# DIO-BNC.net
KiCad netlist of a schematic drawn in Altium Designer
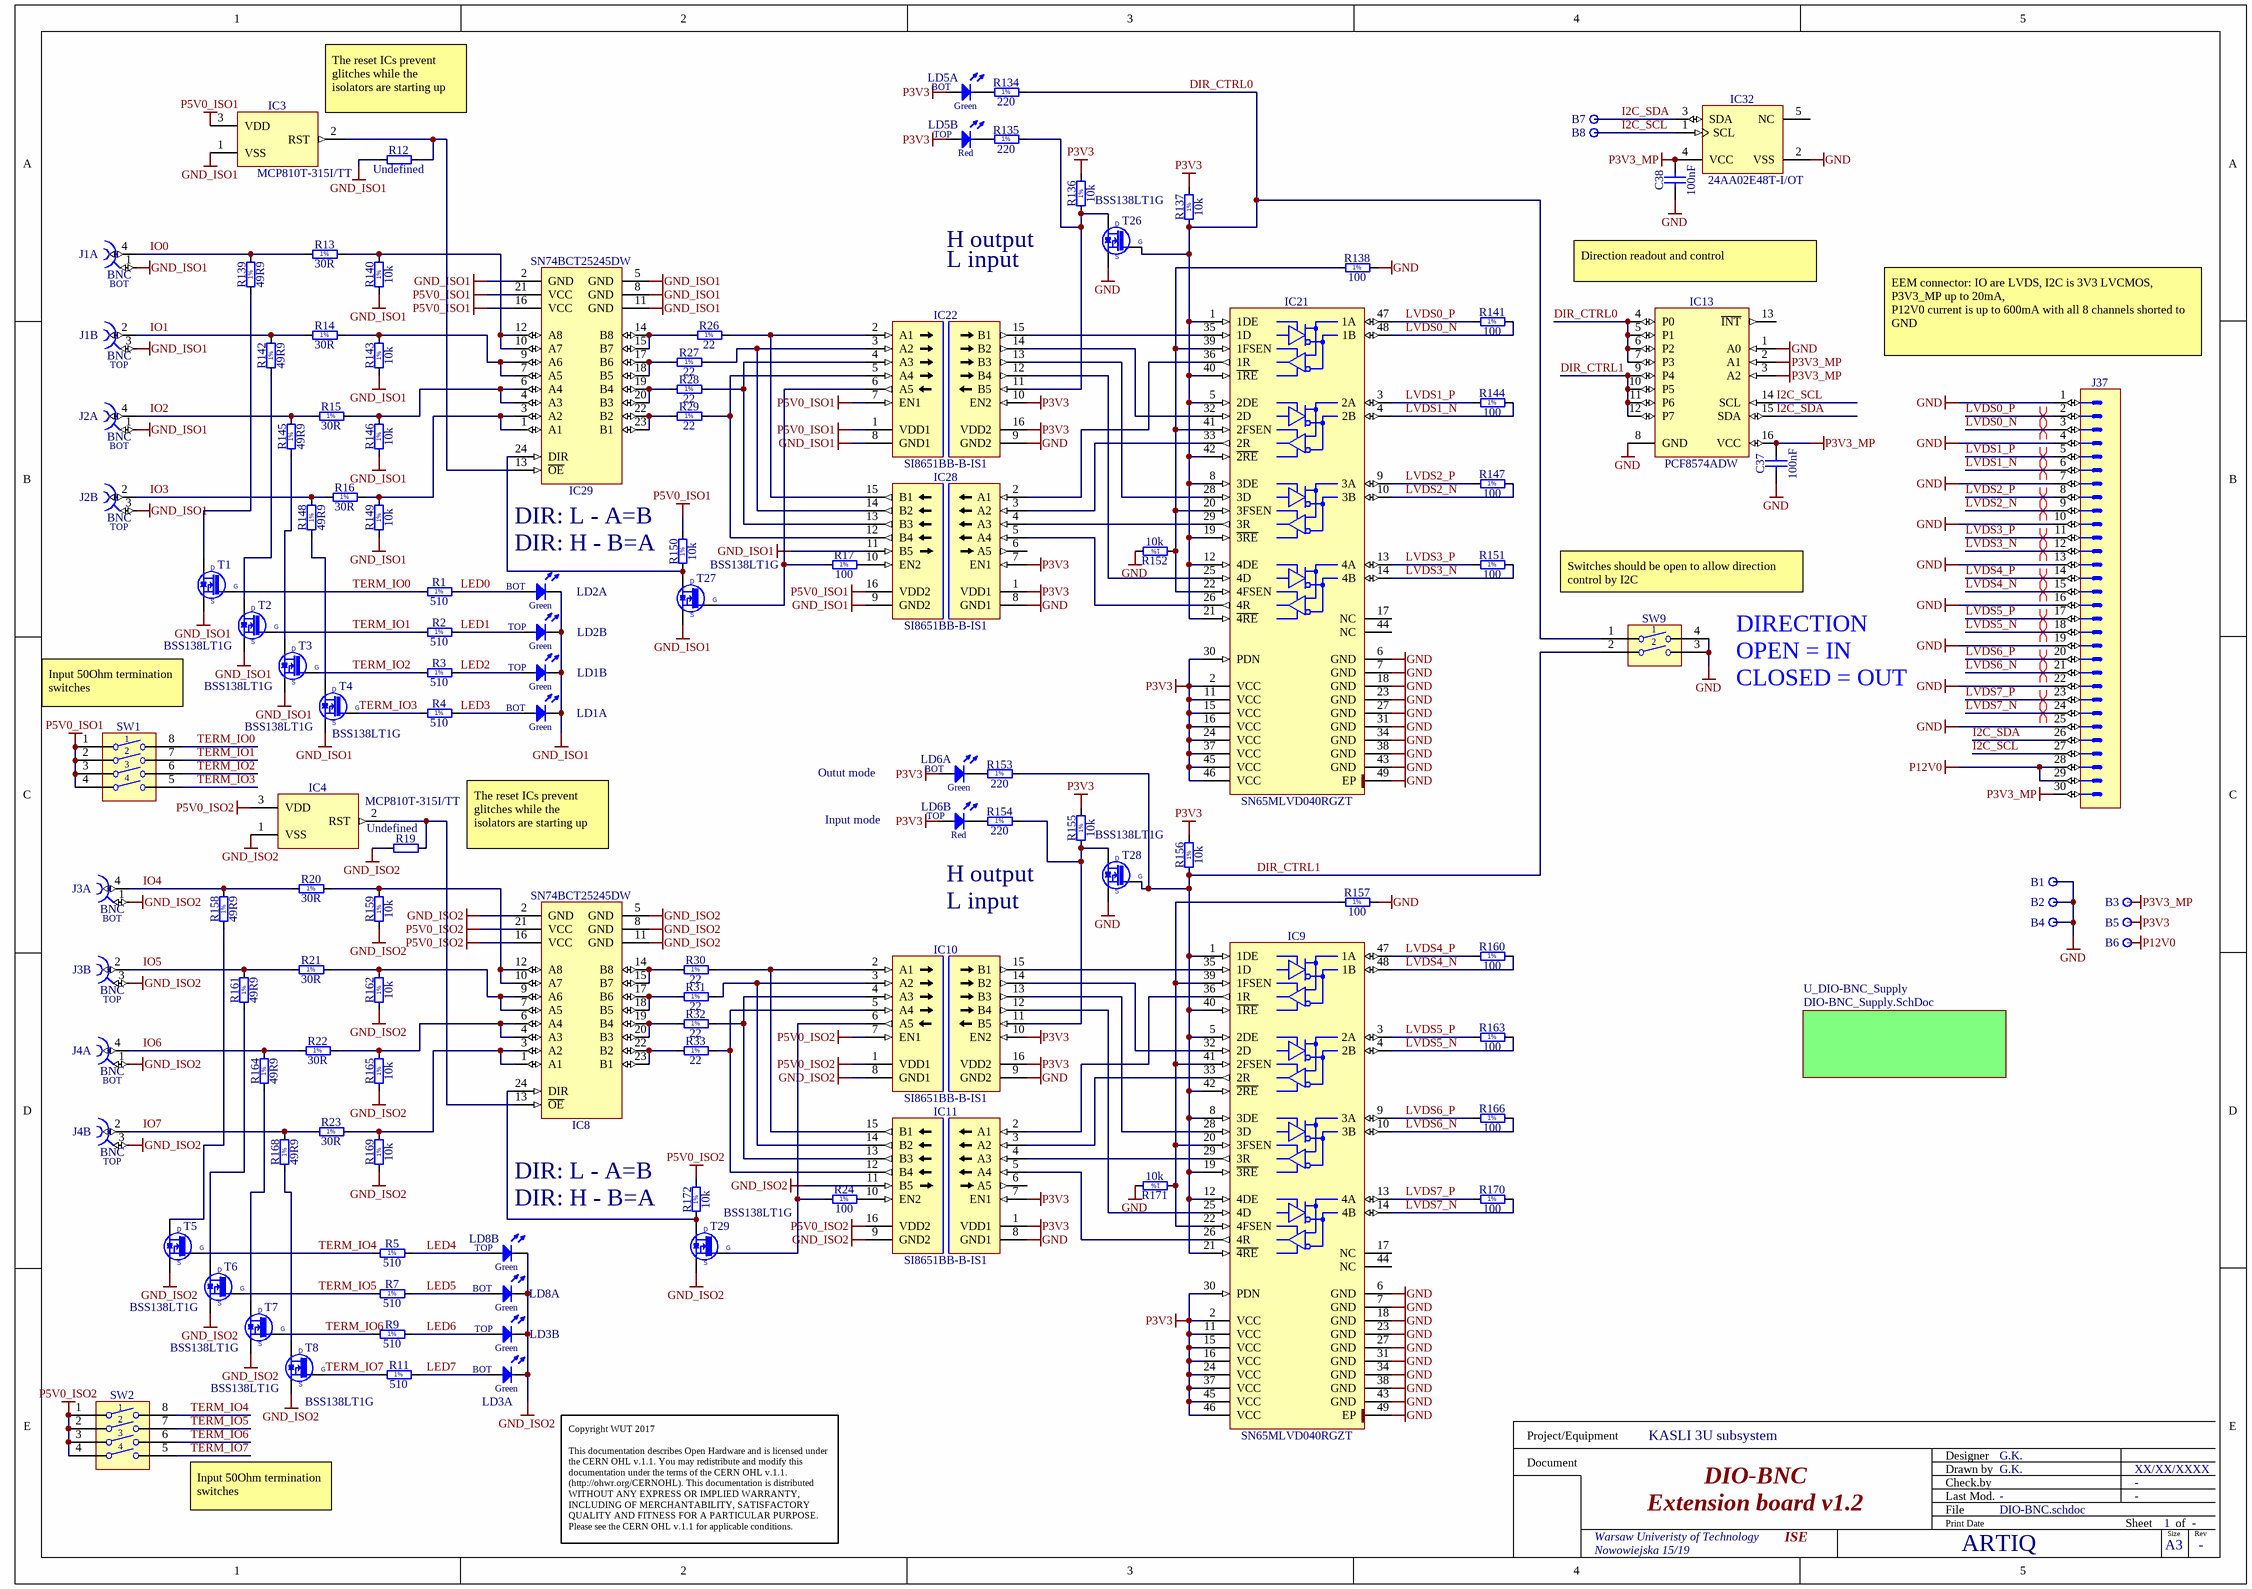
[diagram p0: DIO-BNC.schdoc]

(export (version "E")
  (design (tool "Eeschema 10.0.6"))
  (components
    (comp (ref "B1")
      (value "Plated Hole")
      (footprint "c130h60")
      (description "Single Terminal Socket")
      (fields (field (name "PART NUMBER") "PLATED_HOLE0.6_PAD1.3") (field (name "AUTHOR") "CERN DEM MR"))
      (libsource (lib "Eletro-mechanical") (part "Single Terminal Socket"))
    )
    (comp (ref "B2")
      (value "Plated Hole")
      (footprint "c130h60")
      (description "Single Terminal Socket")
      (fields (field (name "PART NUMBER") "PLATED_HOLE0.6_PAD1.3") (field (name "AUTHOR") "CERN DEM MR"))
      (libsource (lib "Eletro-mechanical") (part "Single Terminal Socket"))
    )
    (comp (ref "B3")
      (value "Plated Hole")
      (footprint "c130h60")
      (description "Single Terminal Socket")
      (fields (field (name "PART NUMBER") "PLATED_HOLE0.6_PAD1.3") (field (name "AUTHOR") "CERN DEM MR"))
      (libsource (lib "Eletro-mechanical") (part "Single Terminal Socket"))
    )
    (comp (ref "B4")
      (value "Plated Hole")
      (footprint "c130h60")
      (description "Single Terminal Socket")
      (fields (field (name "PART NUMBER") "PLATED_HOLE0.6_PAD1.3") (field (name "AUTHOR") "CERN DEM MR"))
      (libsource (lib "Eletro-mechanical") (part "Single Terminal Socket"))
    )
    (comp (ref "B5")
      (value "Plated Hole")
      (footprint "c130h60")
      (description "Single Terminal Socket")
      (fields (field (name "PART NUMBER") "PLATED_HOLE0.6_PAD1.3") (field (name "AUTHOR") "CERN DEM MR"))
      (libsource (lib "Eletro-mechanical") (part "Single Terminal Socket"))
    )
    (comp (ref "B6")
      (value "Plated Hole")
      (footprint "c130h60")
      (description "Single Terminal Socket")
      (fields (field (name "PART NUMBER") "PLATED_HOLE0.6_PAD1.3") (field (name "AUTHOR") "CERN DEM MR"))
      (libsource (lib "Eletro-mechanical") (part "Single Terminal Socket"))
    )
    (comp (ref "B7")
      (value "Plated Hole")
      (footprint "c130h60")
      (description "Single Terminal Socket")
      (fields (field (name "PART NUMBER") "PLATED_HOLE0.6_PAD1.3") (field (name "AUTHOR") "CERN DEM MR"))
      (libsource (lib "Eletro-mechanical") (part "Single Terminal Socket"))
    )
    (comp (ref "B8")
      (value "Plated Hole")
      (footprint "c130h60")
      (description "Single Terminal Socket")
      (fields (field (name "PART NUMBER") "PLATED_HOLE0.6_PAD1.3") (field (name "AUTHOR") "CERN DEM MR"))
      (libsource (lib "Eletro-mechanical") (part "Single Terminal Socket"))
    )
    (comp (ref "C37")
      (value "100nF")
      (footprint "CAPC1005X55N")
      (description "Non-polarised capacitor")
      (fields
        (field (name "PART NUMBER") "CC0402_100NF_16V_10%_X5R")
        (field (name "VOLTAGE") "16V")
        (field (name "AUTHOR") "CERN DEM JLC")
      )
      (libsource (lib "Capacitors") (part "Capacitor - non polarized"))
    )
    (comp (ref "C38")
      (value "100nF")
      (footprint "CAPC1005X55N")
      (description "Non-polarised capacitor")
      (fields
        (field (name "PART NUMBER") "CC0402_100NF_16V_10%_X5R")
        (field (name "VOLTAGE") "16V")
        (field (name "AUTHOR") "CERN DEM JLC")
      )
      (libsource (lib "Capacitors") (part "Capacitor - non polarized"))
    )
    (comp (ref "IC3")
      (value "MCP810T-315I/TT")
      (footprint "SOT95P237X112-3N")
      (description "3.075V Microcontroller Supervisory Circuit With Push-Pull Output")
      (fields (field (name "MANUFACTURER") "MICROCHIP TECHNOLOGY") (field (name "AUTHOR") "GK"))
      (libsource (lib "LIBRARY_SCH") (part "VMON_MCP810"))
    )
    (comp (ref "IC4")
      (value "MCP810T-315I/TT")
      (footprint "SOT95P237X112-3N")
      (description "3.075V Microcontroller Supervisory Circuit With Push-Pull Output")
      (fields (field (name "MANUFACTURER") "MICROCHIP TECHNOLOGY") (field (name "AUTHOR") "GK"))
      (libsource (lib "LIBRARY_SCH") (part "VMON_MCP810"))
    )
    (comp (ref "IC8")
      (value "SN74BCT25245DW")
      (footprint "SOIC127P1030X265-24N")
      (description "25 Ohms Octal Bus Transceiver With 3-State Outputs")
      (fields (field (name "MANUFACTURER") "TEXAS INSTRUMENTS") (field (name "AUTHOR") "CERN DEM JLC"))
      (libsource (lib "ICs And Semiconductors") (part "7425245"))
    )
    (comp (ref "IC9")
      (value "SN65MLVD040RGZT")
      (footprint "QFN50P700X700X100-49N-S420")
      (description "4-Channel Half-Duplex M-LVDS Line Transceiver")
      (fields (field (name "MANUFACTURER") "TEXAS INSTRUMENTS") (field (name "AUTHOR") "CERN DEM JLC"))
      (libsource (lib "ICs And Semiconductors") (part "SN65MLVD040"))
    )
    (comp (ref "IC10")
      (value "SI8651BB-B-IS1")
      (footprint "SOIC127P600X175-16N")
      (description "Low Power Five-Channel Digital Isolator")
      (fields (field (name "MANUFACTURER") "SILICON LABS") (field (name "AUTHOR") "CERN DEM JLC"))
      (libsource (lib "") (part "Si8651_1"))
    )
    (comp (ref "IC11")
      (value "SI8651BB-B-IS1")
      (footprint "SOIC127P600X175-16N")
      (description "Low Power Five-Channel Digital Isolator")
      (fields (field (name "MANUFACTURER") "SILICON LABS") (field (name "AUTHOR") "CERN DEM JLC"))
      (libsource (lib "ICs And Semiconductors") (part "Si8651"))
    )
    (comp (ref "IC13")
      (value "PCF8574ADW")
      (footprint "SOIC127P1030X265-16N")
      (description "Remote 8-bit I/O Expander For I2C Bus")
      (fields (field (name "MANUFACTURER") "TEXAS INSTRUMENTS") (field (name "AUTHOR") "CERN DEM JLC"))
      (libsource (lib "ICs And Semiconductors") (part "PCF8574ADW"))
    )
    (comp (ref "IC21")
      (value "SN65MLVD040RGZT")
      (footprint "QFN50P700X700X100-49N-S420")
      (description "4-Channel Half-Duplex M-LVDS Line Transceiver")
      (fields (field (name "MANUFACTURER") "TEXAS INSTRUMENTS") (field (name "AUTHOR") "CERN DEM JLC"))
      (libsource (lib "ICs And Semiconductors") (part "SN65MLVD040"))
    )
    (comp (ref "IC22")
      (value "SI8651BB-B-IS1")
      (footprint "SOIC127P600X175-16N")
      (description "Low Power Five-Channel Digital Isolator")
      (fields (field (name "MANUFACTURER") "SILICON LABS") (field (name "AUTHOR") "CERN DEM JLC"))
      (libsource (lib "") (part "Si8651_1"))
    )
    (comp (ref "IC28")
      (value "SI8651BB-B-IS1")
      (footprint "SOIC127P600X175-16N")
      (description "Low Power Five-Channel Digital Isolator")
      (fields (field (name "MANUFACTURER") "SILICON LABS") (field (name "AUTHOR") "CERN DEM JLC"))
      (libsource (lib "ICs And Semiconductors") (part "Si8651"))
    )
    (comp (ref "IC29")
      (value "SN74BCT25245DW")
      (footprint "SOIC127P1030X265-24N")
      (description "25 Ohms Octal Bus Transceiver With 3-State Outputs")
      (fields (field (name "MANUFACTURER") "TEXAS INSTRUMENTS") (field (name "AUTHOR") "CERN DEM JLC"))
      (libsource (lib "ICs And Semiconductors") (part "7425245"))
    )
    (comp (ref "IC32")
      (value "24AA02E48T-I/OT")
      (footprint "SOT95P280X145-5N")
      (description "1.7V-5.5V, 2K I2C Serial EEPROM With EUI-48 Node Identity")
      (fields (field (name "MANUFACTURER") "MICROCHIP TECHNOLOGY") (field (name "AUTHOR") "CERN DEM MR"))
      (libsource (lib "ICs And Semiconductors") (part "24AA02E48T-I/OT"))
    )
    (comp (ref "J1")
      (value "BNC")
      (footprint "RENHOTEC_RHT-610-0049")
      (description "Dual Right Angle 50 Ohm BNC Jack, White Valox Case")
      (fields
        (field (name "PART NUMBER") "RENHOTEC_RHT-610-0049")
        (field (name "MANUFACTURER") "RENHOTEC")
        (field (name "AUTHOR") "GK")
      )
      (libsource (lib "LIBRARY_SCH") (part "CON_BNC_DUAL"))
    )
    (comp (ref "J2")
      (value "BNC")
      (footprint "RENHOTEC_RHT-610-0049")
      (description "Dual Right Angle 50 Ohm BNC Jack, White Valox Case")
      (fields
        (field (name "PART NUMBER") "RENHOTEC_RHT-610-0049")
        (field (name "MANUFACTURER") "RENHOTEC")
        (field (name "AUTHOR") "GK")
      )
      (libsource (lib "LIBRARY_SCH") (part "CON_BNC_DUAL"))
    )
    (comp (ref "J3")
      (value "BNC")
      (footprint "RENHOTEC_RHT-610-0049")
      (description "Dual Right Angle 50 Ohm BNC Jack, White Valox Case")
      (fields
        (field (name "PART NUMBER") "RENHOTEC_RHT-610-0049")
        (field (name "MANUFACTURER") "RENHOTEC")
        (field (name "AUTHOR") "GK")
      )
      (libsource (lib "LIBRARY_SCH") (part "CON_BNC_DUAL"))
    )
    (comp (ref "J4")
      (value "BNC")
      (footprint "RENHOTEC_RHT-610-0049")
      (description "Dual Right Angle 50 Ohm BNC Jack, White Valox Case")
      (fields
        (field (name "PART NUMBER") "RENHOTEC_RHT-610-0049")
        (field (name "MANUFACTURER") "RENHOTEC")
        (field (name "AUTHOR") "GK")
      )
      (libsource (lib "LIBRARY_SCH") (part "CON_BNC_DUAL"))
    )
    (comp (ref "J37")
      (value "~")
      (footprint "3M_N2530-6002RB")
      (description "Connector 30 Male")
      (fields
        (field (name "PART NUMBER") "3M_N2530-6002RB")
        (field (name "MANUFACTURER") "3M")
        (field (name "AUTHOR") "CERN DEM JLC")
      )
      (libsource (lib "Connectors") (part "Connector 30 Male"))
    )
    (comp (ref "LD1")
      (value "Green/Green")
      (footprint "LED_DIALIGHT_571-0122F")
      (description "LED x2 Green 1C2A-BOT_3C4A-TOP")
      (fields
        (field (name "PART NUMBER") "LED_DIALIGHT_571-0122F")
        (field (name "MANUFACTURER") "DIALIGHT")
        (field (name "AUTHOR") "CERN DEM JLC")
      )
      (libsource (lib "ICs And Semiconductors") (part "LED x2 Green 1C2A-BOT_3C4A-TOP"))
    )
    (comp (ref "LD2")
      (value "Green/Green")
      (footprint "LED_DIALIGHT_571-0122F")
      (description "LED x2 Green 1C2A-BOT_3C4A-TOP")
      (fields
        (field (name "PART NUMBER") "LED_DIALIGHT_571-0122F")
        (field (name "MANUFACTURER") "DIALIGHT")
        (field (name "AUTHOR") "CERN DEM JLC")
      )
      (libsource (lib "ICs And Semiconductors") (part "LED x2 Green 1C2A-BOT_3C4A-TOP"))
    )
    (comp (ref "LD3")
      (value "Green/Green")
      (footprint "LED_DIALIGHT_571-0122F")
      (description "LED x2 Green 1C2A-BOT_3C4A-TOP")
      (fields
        (field (name "PART NUMBER") "LED_DIALIGHT_571-0122F")
        (field (name "MANUFACTURER") "DIALIGHT")
        (field (name "AUTHOR") "CERN DEM JLC")
      )
      (libsource (lib "ICs And Semiconductors") (part "LED x2 Green 1C2A-BOT_3C4A-TOP"))
    )
    (comp (ref "LD5")
      (value "Red/Green")
      (footprint "LED_DIALIGHT_571-0112F")
      (description "2x LED  Botom Green, Top Red")
      (fields
        (field (name "PART NUMBER") "LED_DIALIGHT_571-0112F")
        (field (name "MANUFACTURER") "DIALIGHT")
        (field (name "AUTHOR") "CERN DEM JLC")
      )
      (libsource (lib "ICs And Semiconductors") (part "LED x2 G-1C2A-BOT_R-3C4A-TOP"))
    )
    (comp (ref "LD6")
      (value "Red/Green")
      (footprint "LED_DIALIGHT_571-0112F")
      (description "2x LED  Botom Green, Top Red")
      (fields
        (field (name "PART NUMBER") "LED_DIALIGHT_571-0112F")
        (field (name "MANUFACTURER") "DIALIGHT")
        (field (name "AUTHOR") "CERN DEM JLC")
      )
      (libsource (lib "ICs And Semiconductors") (part "LED x2 G-1C2A-BOT_R-3C4A-TOP"))
    )
    (comp (ref "LD8")
      (value "Green/Green")
      (footprint "LED_DIALIGHT_571-0122F")
      (description "LED x2 Green 1C2A-BOT_3C4A-TOP")
      (fields
        (field (name "PART NUMBER") "LED_DIALIGHT_571-0122F")
        (field (name "MANUFACTURER") "DIALIGHT")
        (field (name "AUTHOR") "CERN DEM JLC")
      )
      (libsource (lib "ICs And Semiconductors") (part "LED x2 Green 1C2A-BOT_3C4A-TOP"))
    )
    (comp (ref "R1")
      (value "510")
      (footprint "RESC1005X40N")
      (description "Resistor - 1%")
      (fields
        (field (name "PART NUMBER") "R0402_510R_1%_0.0625W_100PPM")
        (field (name "POWER") "0.0625W")
        (field (name "AUTHOR") "CERN DEM JLC")
      )
      (libsource (lib "Resistors") (part "Resistor - 1%"))
    )
    (comp (ref "R2")
      (value "510")
      (footprint "RESC1005X40N")
      (description "Resistor - 1%")
      (fields
        (field (name "PART NUMBER") "R0402_510R_1%_0.0625W_100PPM")
        (field (name "POWER") "0.0625W")
        (field (name "AUTHOR") "CERN DEM JLC")
      )
      (libsource (lib "Resistors") (part "Resistor - 1%"))
    )
    (comp (ref "R3")
      (value "510")
      (footprint "RESC1005X40N")
      (description "Resistor - 1%")
      (fields
        (field (name "PART NUMBER") "R0402_510R_1%_0.0625W_100PPM")
        (field (name "POWER") "0.0625W")
        (field (name "AUTHOR") "CERN DEM JLC")
      )
      (libsource (lib "Resistors") (part "Resistor - 1%"))
    )
    (comp (ref "R4")
      (value "510")
      (footprint "RESC1005X40N")
      (description "Resistor - 1%")
      (fields
        (field (name "PART NUMBER") "R0402_510R_1%_0.0625W_100PPM")
        (field (name "POWER") "0.0625W")
        (field (name "AUTHOR") "CERN DEM JLC")
      )
      (libsource (lib "Resistors") (part "Resistor - 1%"))
    )
    (comp (ref "R5")
      (value "510")
      (footprint "RESC1005X40N")
      (description "Resistor - 1%")
      (fields
        (field (name "PART NUMBER") "R0402_510R_1%_0.0625W_100PPM")
        (field (name "POWER") "0.0625W")
        (field (name "AUTHOR") "CERN DEM JLC")
      )
      (libsource (lib "Resistors") (part "Resistor - 1%"))
    )
    (comp (ref "R7")
      (value "510")
      (footprint "RESC1005X40N")
      (description "Resistor - 1%")
      (fields
        (field (name "PART NUMBER") "R0402_510R_1%_0.0625W_100PPM")
        (field (name "POWER") "0.0625W")
        (field (name "AUTHOR") "CERN DEM JLC")
      )
      (libsource (lib "Resistors") (part "Resistor - 1%"))
    )
    (comp (ref "R9")
      (value "510")
      (footprint "RESC1005X40N")
      (description "Resistor - 1%")
      (fields
        (field (name "PART NUMBER") "R0402_510R_1%_0.0625W_100PPM")
        (field (name "POWER") "0.0625W")
        (field (name "AUTHOR") "CERN DEM JLC")
      )
      (libsource (lib "Resistors") (part "Resistor - 1%"))
    )
    (comp (ref "R11")
      (value "510")
      (footprint "RESC1005X40N")
      (description "Resistor - 1%")
      (fields
        (field (name "PART NUMBER") "R0402_510R_1%_0.0625W_100PPM")
        (field (name "POWER") "0.0625W")
        (field (name "AUTHOR") "CERN DEM JLC")
      )
      (libsource (lib "Resistors") (part "Resistor - 1%"))
    )
    (comp (ref "R12")
      (value "Undefined")
      (footprint "RESC1005X40N")
      (description "Resistor")
      (fields (field (name "PART NUMBER") "R0402_NO-VALUE") (field (name "AUTHOR") "CERN DEM JLC"))
      (libsource (lib "Resistors") (part "Resistor"))
    )
    (comp (ref "R13")
      (value "30R")
      (footprint "RESC3225X70N")
      (description "Resistor - 5%")
      (fields
        (field (name "PART NUMBER") "R1210_30R_5%_0.5W_200ppm")
        (field (name "POWER") "0.5W")
        (field (name "AUTHOR") "CERN DEM JMW")
      )
      (libsource (lib "LIBRARY_SCH") (part "R1210_30R_5%_0.5W_200PPM"))
    )
    (comp (ref "R14")
      (value "30R")
      (footprint "RESC3225X70N")
      (description "Resistor - 5%")
      (fields
        (field (name "PART NUMBER") "R1210_30R_5%_0.5W_200ppm")
        (field (name "POWER") "0.5W")
        (field (name "AUTHOR") "CERN DEM JMW")
      )
      (libsource (lib "LIBRARY_SCH") (part "R1210_30R_5%_0.5W_200PPM"))
    )
    (comp (ref "R15")
      (value "30R")
      (footprint "RESC3225X70N")
      (description "Resistor - 5%")
      (fields
        (field (name "PART NUMBER") "R1210_30R_5%_0.5W_200ppm")
        (field (name "POWER") "0.5W")
        (field (name "AUTHOR") "CERN DEM JMW")
      )
      (libsource (lib "LIBRARY_SCH") (part "R1210_30R_5%_0.5W_200PPM"))
    )
    (comp (ref "R16")
      (value "30R")
      (footprint "RESC3225X70N")
      (description "Resistor - 5%")
      (fields
        (field (name "PART NUMBER") "R1210_30R_5%_0.5W_200ppm")
        (field (name "POWER") "0.5W")
        (field (name "AUTHOR") "CERN DEM JMW")
      )
      (libsource (lib "LIBRARY_SCH") (part "R1210_30R_5%_0.5W_200PPM"))
    )
    (comp (ref "R17")
      (value "100")
      (footprint "RESC1005X40N")
      (description "Resistor - 1%")
      (fields
        (field (name "PART NUMBER") "R0402_100R_1%_0.1W_100PPM")
        (field (name "POWER") "0.1W")
        (field (name "AUTHOR") "CERN DEM JLC")
      )
      (libsource (lib "Resistors") (part "Resistor - 1%"))
    )
    (comp (ref "R19")
      (value "Undefined")
      (footprint "RESC1005X40N")
      (description "Resistor")
      (fields (field (name "PART NUMBER") "R0402_NO-VALUE") (field (name "AUTHOR") "CERN DEM JLC"))
      (libsource (lib "Resistors") (part "Resistor"))
    )
    (comp (ref "R20")
      (value "30R")
      (footprint "RESC3225X70N")
      (description "Resistor - 5%")
      (fields
        (field (name "PART NUMBER") "R1210_30R_5%_0.5W_200ppm")
        (field (name "POWER") "0.5W")
        (field (name "AUTHOR") "CERN DEM JMW")
      )
      (libsource (lib "LIBRARY_SCH") (part "R1210_30R_5%_0.5W_200PPM"))
    )
    (comp (ref "R21")
      (value "30R")
      (footprint "RESC3225X70N")
      (description "Resistor - 5%")
      (fields
        (field (name "PART NUMBER") "R1210_30R_5%_0.5W_200ppm")
        (field (name "POWER") "0.5W")
        (field (name "AUTHOR") "CERN DEM JMW")
      )
      (libsource (lib "LIBRARY_SCH") (part "R1210_30R_5%_0.5W_200PPM"))
    )
    (comp (ref "R22")
      (value "30R")
      (footprint "RESC3225X70N")
      (description "Resistor - 5%")
      (fields
        (field (name "PART NUMBER") "R1210_30R_5%_0.5W_200ppm")
        (field (name "POWER") "0.5W")
        (field (name "AUTHOR") "CERN DEM JMW")
      )
      (libsource (lib "LIBRARY_SCH") (part "R1210_30R_5%_0.5W_200PPM"))
    )
    (comp (ref "R23")
      (value "30R")
      (footprint "RESC3225X70N")
      (description "Resistor - 5%")
      (fields
        (field (name "PART NUMBER") "R1210_30R_5%_0.5W_200ppm")
        (field (name "POWER") "0.5W")
        (field (name "AUTHOR") "CERN DEM JMW")
      )
      (libsource (lib "LIBRARY_SCH") (part "R1210_30R_5%_0.5W_200PPM"))
    )
    (comp (ref "R24")
      (value "100")
      (footprint "RESC1005X40N")
      (description "Resistor - 1%")
      (fields
        (field (name "PART NUMBER") "R0402_100R_1%_0.1W_100PPM")
        (field (name "POWER") "0.1W")
        (field (name "AUTHOR") "CERN DEM JLC")
      )
      (libsource (lib "Resistors") (part "Resistor - 1%"))
    )
    (comp (ref "R26")
      (value "22")
      (footprint "RESC1005X40N")
      (description "Resistor - 1%")
      (fields
        (field (name "PART NUMBER") "R0402_22R_1%_0.0625W_100PPM")
        (field (name "POWER") "0.0625W")
        (field (name "AUTHOR") "CERN DEM JLC")
      )
      (libsource (lib "Resistors") (part "Resistor - 1%"))
    )
    (comp (ref "R27")
      (value "22")
      (footprint "RESC1005X40N")
      (description "Resistor - 1%")
      (fields
        (field (name "PART NUMBER") "R0402_22R_1%_0.0625W_100PPM")
        (field (name "POWER") "0.0625W")
        (field (name "AUTHOR") "CERN DEM JLC")
      )
      (libsource (lib "Resistors") (part "Resistor - 1%"))
    )
    (comp (ref "R28")
      (value "22")
      (footprint "RESC1005X40N")
      (description "Resistor - 1%")
      (fields
        (field (name "PART NUMBER") "R0402_22R_1%_0.0625W_100PPM")
        (field (name "POWER") "0.0625W")
        (field (name "AUTHOR") "CERN DEM JLC")
      )
      (libsource (lib "Resistors") (part "Resistor - 1%"))
    )
    (comp (ref "R29")
      (value "22")
      (footprint "RESC1005X40N")
      (description "Resistor - 1%")
      (fields
        (field (name "PART NUMBER") "R0402_22R_1%_0.0625W_100PPM")
        (field (name "POWER") "0.0625W")
        (field (name "AUTHOR") "CERN DEM JLC")
      )
      (libsource (lib "Resistors") (part "Resistor - 1%"))
    )
    (comp (ref "R30")
      (value "22")
      (footprint "RESC1005X40N")
      (description "Resistor - 1%")
      (fields
        (field (name "PART NUMBER") "R0402_22R_1%_0.0625W_100PPM")
        (field (name "POWER") "0.0625W")
        (field (name "AUTHOR") "CERN DEM JLC")
      )
      (libsource (lib "Resistors") (part "Resistor - 1%"))
    )
    (comp (ref "R31")
      (value "22")
      (footprint "RESC1005X40N")
      (description "Resistor - 1%")
      (fields
        (field (name "PART NUMBER") "R0402_22R_1%_0.0625W_100PPM")
        (field (name "POWER") "0.0625W")
        (field (name "AUTHOR") "CERN DEM JLC")
      )
      (libsource (lib "Resistors") (part "Resistor - 1%"))
    )
    (comp (ref "R32")
      (value "22")
      (footprint "RESC1005X40N")
      (description "Resistor - 1%")
      (fields
        (field (name "PART NUMBER") "R0402_22R_1%_0.0625W_100PPM")
        (field (name "POWER") "0.0625W")
        (field (name "AUTHOR") "CERN DEM JLC")
      )
      (libsource (lib "Resistors") (part "Resistor - 1%"))
    )
    (comp (ref "R33")
      (value "22")
      (footprint "RESC1005X40N")
      (description "Resistor - 1%")
      (fields
        (field (name "PART NUMBER") "R0402_22R_1%_0.0625W_100PPM")
        (field (name "POWER") "0.0625W")
        (field (name "AUTHOR") "CERN DEM JLC")
      )
      (libsource (lib "Resistors") (part "Resistor - 1%"))
    )
    (comp (ref "R134")
      (value "220")
      (footprint "RESC1608X55N")
      (description "Resistor - 1%")
      (fields
        (field (name "PART NUMBER") "R0603_220R_1%_0.1W_100PPM")
        (field (name "POWER") "0.1W")
        (field (name "AUTHOR") "CERN DEM JLC")
      )
      (libsource (lib "Resistors") (part "Resistor - 1%"))
    )
    (comp (ref "R135")
      (value "220")
      (footprint "RESC1608X55N")
      (description "Resistor - 1%")
      (fields
        (field (name "PART NUMBER") "R0603_220R_1%_0.1W_100PPM")
        (field (name "POWER") "0.1W")
        (field (name "AUTHOR") "CERN DEM JLC")
      )
      (libsource (lib "Resistors") (part "Resistor - 1%"))
    )
    (comp (ref "R136")
      (value "10k")
      (footprint "RESC1005X40N")
      (description "Resistor - 1%")
      (fields
        (field (name "PART NUMBER") "R0402_10K_1%_0.0625W_100PPM")
        (field (name "POWER") "0.0625W")
        (field (name "AUTHOR") "CERN DEM JLC")
      )
      (libsource (lib "Resistors") (part "Resistor - 1%"))
    )
    (comp (ref "R137")
      (value "10k")
      (footprint "RESC1005X40N")
      (description "Resistor - 1%")
      (fields
        (field (name "PART NUMBER") "R0402_10K_1%_0.0625W_100PPM")
        (field (name "POWER") "0.0625W")
        (field (name "AUTHOR") "CERN DEM JLC")
      )
      (libsource (lib "Resistors") (part "Resistor - 1%"))
    )
    (comp (ref "R138")
      (value "100")
      (footprint "RESC1005X40N")
      (description "Resistor - 1%")
      (fields
        (field (name "PART NUMBER") "R0402_100R_1%_0.1W_100PPM")
        (field (name "POWER") "0.1W")
        (field (name "AUTHOR") "CERN DEM JLC")
      )
      (libsource (lib "Resistors") (part "Resistor - 1%"))
    )
    (comp (ref "R139")
      (value "49R9")
      (footprint "RESC3225X70N")
      (description "Resistor - 1%")
      (fields
        (field (name "PART NUMBER") "R1210_49R9_1%_0.5W_100PPM_VISHAY_CRCW")
        (field (name "POWER") "0.5W")
        (field (name "AUTHOR") "CERN DEM JMW")
      )
      (libsource (lib "Resistors") (part "Resistor - 1%"))
    )
    (comp (ref "R140")
      (value "10k")
      (footprint "RESC1005X40N")
      (description "Resistor - 1%")
      (fields
        (field (name "PART NUMBER") "R0402_10K_1%_0.0625W_100PPM")
        (field (name "POWER") "0.0625W")
        (field (name "AUTHOR") "CERN DEM JLC")
      )
      (libsource (lib "Resistors") (part "Resistor - 1%"))
    )
    (comp (ref "R141")
      (value "100")
      (footprint "RESC1005X40N")
      (description "Resistor - 1%")
      (fields
        (field (name "PART NUMBER") "R0402_100R_1%_0.1W_100PPM")
        (field (name "POWER") "0.1W")
        (field (name "AUTHOR") "CERN DEM JLC")
      )
      (libsource (lib "Resistors") (part "Resistor - 1%"))
    )
    (comp (ref "R142")
      (value "49R9")
      (footprint "RESC3225X70N")
      (description "Resistor - 1%")
      (fields
        (field (name "PART NUMBER") "R1210_49R9_1%_0.5W_100PPM_VISHAY_CRCW")
        (field (name "POWER") "0.5W")
        (field (name "AUTHOR") "CERN DEM JMW")
      )
      (libsource (lib "Resistors") (part "Resistor - 1%"))
    )
    (comp (ref "R143")
      (value "10k")
      (footprint "RESC1005X40N")
      (description "Resistor - 1%")
      (fields
        (field (name "PART NUMBER") "R0402_10K_1%_0.0625W_100PPM")
        (field (name "POWER") "0.0625W")
        (field (name "AUTHOR") "CERN DEM JLC")
      )
      (libsource (lib "Resistors") (part "Resistor - 1%"))
    )
    (comp (ref "R144")
      (value "100")
      (footprint "RESC1005X40N")
      (description "Resistor - 1%")
      (fields
        (field (name "PART NUMBER") "R0402_100R_1%_0.1W_100PPM")
        (field (name "POWER") "0.1W")
        (field (name "AUTHOR") "CERN DEM JLC")
      )
      (libsource (lib "Resistors") (part "Resistor - 1%"))
    )
    (comp (ref "R145")
      (value "49R9")
      (footprint "RESC3225X70N")
      (description "Resistor - 1%")
      (fields
        (field (name "PART NUMBER") "R1210_49R9_1%_0.5W_100PPM_VISHAY_CRCW")
        (field (name "POWER") "0.5W")
        (field (name "AUTHOR") "CERN DEM JMW")
      )
      (libsource (lib "Resistors") (part "Resistor - 1%"))
    )
    (comp (ref "R146")
      (value "10k")
      (footprint "RESC1005X40N")
      (description "Resistor - 1%")
      (fields
        (field (name "PART NUMBER") "R0402_10K_1%_0.0625W_100PPM")
        (field (name "POWER") "0.0625W")
        (field (name "AUTHOR") "CERN DEM JLC")
      )
      (libsource (lib "Resistors") (part "Resistor - 1%"))
    )
    (comp (ref "R147")
      (value "100")
      (footprint "RESC1005X40N")
      (description "Resistor - 1%")
      (fields
        (field (name "PART NUMBER") "R0402_100R_1%_0.1W_100PPM")
        (field (name "POWER") "0.1W")
        (field (name "AUTHOR") "CERN DEM JLC")
      )
      (libsource (lib "Resistors") (part "Resistor - 1%"))
    )
    (comp (ref "R148")
      (value "49R9")
      (footprint "RESC3225X70N")
      (description "Resistor - 1%")
      (fields
        (field (name "PART NUMBER") "R1210_49R9_1%_0.5W_100PPM_VISHAY_CRCW")
        (field (name "POWER") "0.5W")
        (field (name "AUTHOR") "CERN DEM JMW")
      )
      (libsource (lib "Resistors") (part "Resistor - 1%"))
    )
    (comp (ref "R149")
      (value "10k")
      (footprint "RESC1005X40N")
      (description "Resistor - 1%")
      (fields
        (field (name "PART NUMBER") "R0402_10K_1%_0.0625W_100PPM")
        (field (name "POWER") "0.0625W")
        (field (name "AUTHOR") "CERN DEM JLC")
      )
      (libsource (lib "Resistors") (part "Resistor - 1%"))
    )
    (comp (ref "R150")
      (value "10k")
      (footprint "RESC1005X40N")
      (description "Resistor - 1%")
      (fields
        (field (name "PART NUMBER") "R0402_10K_1%_0.0625W_100PPM")
        (field (name "POWER") "0.0625W")
        (field (name "AUTHOR") "CERN DEM JLC")
      )
      (libsource (lib "Resistors") (part "Resistor - 1%"))
    )
    (comp (ref "R151")
      (value "100")
      (footprint "RESC1005X40N")
      (description "Resistor - 1%")
      (fields
        (field (name "PART NUMBER") "R0402_100R_1%_0.1W_100PPM")
        (field (name "POWER") "0.1W")
        (field (name "AUTHOR") "CERN DEM JLC")
      )
      (libsource (lib "Resistors") (part "Resistor - 1%"))
    )
    (comp (ref "R152")
      (value "10k")
      (footprint "RESC1005X40N")
      (description "Resistor - 1%")
      (fields
        (field (name "PART NUMBER") "R0402_10K_1%_0.0625W_100PPM")
        (field (name "POWER") "0.0625W")
        (field (name "AUTHOR") "CERN DEM JLC")
      )
      (libsource (lib "Resistors") (part "Resistor - 1%"))
    )
    (comp (ref "R153")
      (value "220")
      (footprint "RESC1608X55N")
      (description "Resistor - 1%")
      (fields
        (field (name "PART NUMBER") "R0603_220R_1%_0.1W_100PPM")
        (field (name "POWER") "0.1W")
        (field (name "AUTHOR") "CERN DEM JLC")
      )
      (libsource (lib "Resistors") (part "Resistor - 1%"))
    )
    (comp (ref "R154")
      (value "220")
      (footprint "RESC1608X55N")
      (description "Resistor - 1%")
      (fields
        (field (name "PART NUMBER") "R0603_220R_1%_0.1W_100PPM")
        (field (name "POWER") "0.1W")
        (field (name "AUTHOR") "CERN DEM JLC")
      )
      (libsource (lib "Resistors") (part "Resistor - 1%"))
    )
    (comp (ref "R155")
      (value "10k")
      (footprint "RESC1005X40N")
      (description "Resistor - 1%")
      (fields
        (field (name "PART NUMBER") "R0402_10K_1%_0.0625W_100PPM")
        (field (name "POWER") "0.0625W")
        (field (name "AUTHOR") "CERN DEM JLC")
      )
      (libsource (lib "Resistors") (part "Resistor - 1%"))
    )
    (comp (ref "R156")
      (value "10k")
      (footprint "RESC1005X40N")
      (description "Resistor - 1%")
      (fields
        (field (name "PART NUMBER") "R0402_10K_1%_0.0625W_100PPM")
        (field (name "POWER") "0.0625W")
        (field (name "AUTHOR") "CERN DEM JLC")
      )
      (libsource (lib "Resistors") (part "Resistor - 1%"))
    )
    (comp (ref "R157")
      (value "100")
      (footprint "RESC1005X40N")
      (description "Resistor - 1%")
      (fields
        (field (name "PART NUMBER") "R0402_100R_1%_0.1W_100PPM")
        (field (name "POWER") "0.1W")
        (field (name "AUTHOR") "CERN DEM JLC")
      )
      (libsource (lib "Resistors") (part "Resistor - 1%"))
    )
    (comp (ref "R158")
      (value "49R9")
      (footprint "RESC3225X70N")
      (description "Resistor - 1%")
      (fields
        (field (name "PART NUMBER") "R1210_49R9_1%_0.5W_100PPM_VISHAY_CRCW")
        (field (name "POWER") "0.5W")
        (field (name "AUTHOR") "CERN DEM JMW")
      )
      (libsource (lib "Resistors") (part "Resistor - 1%"))
    )
    (comp (ref "R159")
      (value "10k")
      (footprint "RESC1005X40N")
      (description "Resistor - 1%")
      (fields
        (field (name "PART NUMBER") "R0402_10K_1%_0.0625W_100PPM")
        (field (name "POWER") "0.0625W")
        (field (name "AUTHOR") "CERN DEM JLC")
      )
      (libsource (lib "Resistors") (part "Resistor - 1%"))
    )
    (comp (ref "R160")
      (value "100")
      (footprint "RESC1005X40N")
      (description "Resistor - 1%")
      (fields
        (field (name "PART NUMBER") "R0402_100R_1%_0.1W_100PPM")
        (field (name "POWER") "0.1W")
        (field (name "AUTHOR") "CERN DEM JLC")
      )
      (libsource (lib "Resistors") (part "Resistor - 1%"))
    )
    (comp (ref "R161")
      (value "49R9")
      (footprint "RESC3225X70N")
      (description "Resistor - 1%")
      (fields
        (field (name "PART NUMBER") "R1210_49R9_1%_0.5W_100PPM_VISHAY_CRCW")
        (field (name "POWER") "0.5W")
        (field (name "AUTHOR") "CERN DEM JMW")
      )
      (libsource (lib "Resistors") (part "Resistor - 1%"))
    )
    (comp (ref "R162")
      (value "10k")
      (footprint "RESC1005X40N")
      (description "Resistor - 1%")
      (fields
        (field (name "PART NUMBER") "R0402_10K_1%_0.0625W_100PPM")
        (field (name "POWER") "0.0625W")
        (field (name "AUTHOR") "CERN DEM JLC")
      )
      (libsource (lib "Resistors") (part "Resistor - 1%"))
    )
    (comp (ref "R163")
      (value "100")
      (footprint "RESC1005X40N")
      (description "Resistor - 1%")
      (fields
        (field (name "PART NUMBER") "R0402_100R_1%_0.1W_100PPM")
        (field (name "POWER") "0.1W")
        (field (name "AUTHOR") "CERN DEM JLC")
      )
      (libsource (lib "Resistors") (part "Resistor - 1%"))
    )
    (comp (ref "R164")
      (value "49R9")
      (footprint "RESC3225X70N")
      (description "Resistor - 1%")
      (fields
        (field (name "PART NUMBER") "R1210_49R9_1%_0.5W_100PPM_VISHAY_CRCW")
        (field (name "POWER") "0.5W")
        (field (name "AUTHOR") "CERN DEM JMW")
      )
      (libsource (lib "Resistors") (part "Resistor - 1%"))
    )
    (comp (ref "R165")
      (value "10k")
      (footprint "RESC1005X40N")
      (description "Resistor - 1%")
      (fields
        (field (name "PART NUMBER") "R0402_10K_1%_0.0625W_100PPM")
        (field (name "POWER") "0.0625W")
        (field (name "AUTHOR") "CERN DEM JLC")
      )
      (libsource (lib "Resistors") (part "Resistor - 1%"))
    )
    (comp (ref "R166")
      (value "100")
      (footprint "RESC1005X40N")
      (description "Resistor - 1%")
      (fields
        (field (name "PART NUMBER") "R0402_100R_1%_0.1W_100PPM")
        (field (name "POWER") "0.1W")
        (field (name "AUTHOR") "CERN DEM JLC")
      )
      (libsource (lib "Resistors") (part "Resistor - 1%"))
    )
    (comp (ref "R168")
      (value "49R9")
      (footprint "RESC3225X70N")
      (description "Resistor - 1%")
      (fields
        (field (name "PART NUMBER") "R1210_49R9_1%_0.5W_100PPM_VISHAY_CRCW")
        (field (name "POWER") "0.5W")
        (field (name "AUTHOR") "CERN DEM JMW")
      )
      (libsource (lib "Resistors") (part "Resistor - 1%"))
    )
    (comp (ref "R169")
      (value "10k")
      (footprint "RESC1005X40N")
      (description "Resistor - 1%")
      (fields
        (field (name "PART NUMBER") "R0402_10K_1%_0.0625W_100PPM")
        (field (name "POWER") "0.0625W")
        (field (name "AUTHOR") "CERN DEM JLC")
      )
      (libsource (lib "Resistors") (part "Resistor - 1%"))
    )
    (comp (ref "R170")
      (value "100")
      (footprint "RESC1005X40N")
      (description "Resistor - 1%")
      (fields
        (field (name "PART NUMBER") "R0402_100R_1%_0.1W_100PPM")
        (field (name "POWER") "0.1W")
        (field (name "AUTHOR") "CERN DEM JLC")
      )
      (libsource (lib "Resistors") (part "Resistor - 1%"))
    )
    (comp (ref "R171")
      (value "10k")
      (footprint "RESC1005X40N")
      (description "Resistor - 1%")
      (fields
        (field (name "PART NUMBER") "R0402_10K_1%_0.0625W_100PPM")
        (field (name "POWER") "0.0625W")
        (field (name "AUTHOR") "CERN DEM JLC")
      )
      (libsource (lib "Resistors") (part "Resistor - 1%"))
    )
    (comp (ref "R172")
      (value "10k")
      (footprint "RESC1005X40N")
      (description "Resistor - 1%")
      (fields
        (field (name "PART NUMBER") "R0402_10K_1%_0.0625W_100PPM")
        (field (name "POWER") "0.0625W")
        (field (name "AUTHOR") "CERN DEM JLC")
      )
      (libsource (lib "Resistors") (part "Resistor - 1%"))
    )
    (comp (ref "SW1")
      (value "Switch")
      (footprint "SW_OMRON_A6S-4102-H")
      (description "4 Ways SPST DIP Switch")
      (fields
        (field (name "PART NUMBER") "SW_OMRON_A6S-4102-H")
        (field (name "MANUFACTURER") "OMRON")
        (field (name "AUTHOR") "CERN DEM JMW")
      )
      (libsource (lib "Eletro-mechanical") (part "SW 4x SPST DIP Switch"))
    )
    (comp (ref "SW2")
      (value "Switch")
      (footprint "SW_OMRON_A6S-4102-H")
      (description "4 Ways SPST DIP Switch")
      (fields
        (field (name "PART NUMBER") "SW_OMRON_A6S-4102-H")
        (field (name "MANUFACTURER") "OMRON")
        (field (name "AUTHOR") "CERN DEM JMW")
      )
      (libsource (lib "Eletro-mechanical") (part "SW 4x SPST DIP Switch"))
    )
    (comp (ref "SW9")
      (value "Switch")
      (footprint "SW_OMRON_A6S-2102-H")
      (description "2 Ways SPST DIP Switch")
      (fields
        (field (name "PART NUMBER") "SW_OMRON_A6S-2102-H")
        (field (name "MANUFACTURER") "OMRON")
        (field (name "AUTHOR") "CERN DEM JMW")
      )
      (libsource (lib "Eletro-mechanical") (part "SW 2x SPST DIP Switch"))
    )
    (comp (ref "T1")
      (value "BSS138LT1G")
      (footprint "SOT95P240X110-3N")
      (description "N-CHANNEL MOSFET WITH DIODE")
      (fields (field (name "MANUFACTURER") "ON SEMICONDUCTOR") (field (name "AUTHOR") "CERN DEM JLC"))
      (libsource (lib "ICs And Semiconductors") (part "N-MOSFET-D 1G 2S 3D"))
    )
    (comp (ref "T2")
      (value "BSS138LT1G")
      (footprint "SOT95P240X110-3N")
      (description "N-CHANNEL MOSFET WITH DIODE")
      (fields (field (name "MANUFACTURER") "ON SEMICONDUCTOR") (field (name "AUTHOR") "CERN DEM JLC"))
      (libsource (lib "ICs And Semiconductors") (part "N-MOSFET-D 1G 2S 3D"))
    )
    (comp (ref "T3")
      (value "BSS138LT1G")
      (footprint "SOT95P240X110-3N")
      (description "N-CHANNEL MOSFET WITH DIODE")
      (fields (field (name "MANUFACTURER") "ON SEMICONDUCTOR") (field (name "AUTHOR") "CERN DEM JLC"))
      (libsource (lib "ICs And Semiconductors") (part "N-MOSFET-D 1G 2S 3D"))
    )
    (comp (ref "T4")
      (value "BSS138LT1G")
      (footprint "SOT95P240X110-3N")
      (description "N-CHANNEL MOSFET WITH DIODE")
      (fields (field (name "MANUFACTURER") "ON SEMICONDUCTOR") (field (name "AUTHOR") "CERN DEM JLC"))
      (libsource (lib "ICs And Semiconductors") (part "N-MOSFET-D 1G 2S 3D"))
    )
    (comp (ref "T5")
      (value "BSS138LT1G")
      (footprint "SOT95P240X110-3N")
      (description "N-CHANNEL MOSFET WITH DIODE")
      (fields (field (name "MANUFACTURER") "ON SEMICONDUCTOR") (field (name "AUTHOR") "CERN DEM JLC"))
      (libsource (lib "ICs And Semiconductors") (part "N-MOSFET-D 1G 2S 3D"))
    )
    (comp (ref "T6")
      (value "BSS138LT1G")
      (footprint "SOT95P240X110-3N")
      (description "N-CHANNEL MOSFET WITH DIODE")
      (fields (field (name "MANUFACTURER") "ON SEMICONDUCTOR") (field (name "AUTHOR") "CERN DEM JLC"))
      (libsource (lib "ICs And Semiconductors") (part "N-MOSFET-D 1G 2S 3D"))
    )
    (comp (ref "T7")
      (value "BSS138LT1G")
      (footprint "SOT95P240X110-3N")
      (description "N-CHANNEL MOSFET WITH DIODE")
      (fields (field (name "MANUFACTURER") "ON SEMICONDUCTOR") (field (name "AUTHOR") "CERN DEM JLC"))
      (libsource (lib "ICs And Semiconductors") (part "N-MOSFET-D 1G 2S 3D"))
    )
    (comp (ref "T8")
      (value "BSS138LT1G")
      (footprint "SOT95P240X110-3N")
      (description "N-CHANNEL MOSFET WITH DIODE")
      (fields (field (name "MANUFACTURER") "ON SEMICONDUCTOR") (field (name "AUTHOR") "CERN DEM JLC"))
      (libsource (lib "ICs And Semiconductors") (part "N-MOSFET-D 1G 2S 3D"))
    )
    (comp (ref "T26")
      (value "BSS138LT1G")
      (footprint "SOT95P240X110-3N")
      (description "N-CHANNEL MOSFET WITH DIODE")
      (fields (field (name "MANUFACTURER") "ON SEMICONDUCTOR") (field (name "AUTHOR") "CERN DEM JLC"))
      (libsource (lib "ICs And Semiconductors") (part "N-MOSFET-D 1G 2S 3D"))
    )
    (comp (ref "T27")
      (value "BSS138LT1G")
      (footprint "SOT95P240X110-3N")
      (description "N-CHANNEL MOSFET WITH DIODE")
      (fields (field (name "MANUFACTURER") "ON SEMICONDUCTOR") (field (name "AUTHOR") "CERN DEM JLC"))
      (libsource (lib "ICs And Semiconductors") (part "N-MOSFET-D 1G 2S 3D"))
    )
    (comp (ref "T28")
      (value "BSS138LT1G")
      (footprint "SOT95P240X110-3N")
      (description "N-CHANNEL MOSFET WITH DIODE")
      (fields (field (name "MANUFACTURER") "ON SEMICONDUCTOR") (field (name "AUTHOR") "CERN DEM JLC"))
      (libsource (lib "ICs And Semiconductors") (part "N-MOSFET-D 1G 2S 3D"))
    )
    (comp (ref "T29")
      (value "BSS138LT1G")
      (footprint "SOT95P240X110-3N")
      (description "N-CHANNEL MOSFET WITH DIODE")
      (fields (field (name "MANUFACTURER") "ON SEMICONDUCTOR") (field (name "AUTHOR") "CERN DEM JLC"))
      (libsource (lib "ICs And Semiconductors") (part "N-MOSFET-D 1G 2S 3D"))
    )
  )
  (nets
    (net (code "1") (name "/DIR_CTRL0") (class "Default")
      (node (ref "IC13") (pin "4") (pinfunction "P0_4") (pintype "bidirectional"))
      (node (ref "IC13") (pin "5") (pinfunction "P1_5") (pintype "bidirectional"))
      (node (ref "IC13") (pin "6") (pinfunction "P2_6") (pintype "bidirectional"))
      (node (ref "IC13") (pin "7") (pinfunction "P3_7") (pintype "bidirectional"))
      (node (ref "IC21") (pin "1") (pinfunction "1DE_1") (pintype "input"))
      (node (ref "IC21") (pin "12") (pinfunction "4DE_12") (pintype "input"))
      (node (ref "IC21") (pin "19") (pinfunction "~{3RE}_19") (pintype "input"))
      (node (ref "IC21") (pin "21") (pinfunction "~{4RE}_21") (pintype "input"))
      (node (ref "IC21") (pin "40") (pinfunction "~{1RE}_40") (pintype "input"))
      (node (ref "IC21") (pin "42") (pinfunction "~{2RE}_42") (pintype "input"))
      (node (ref "IC21") (pin "5") (pinfunction "2DE_5") (pintype "input"))
      (node (ref "IC21") (pin "8") (pinfunction "3DE_8") (pintype "input"))
      (node (ref "R134") (pin "2") (pinfunction "2_2") (pintype "passive"))
      (node (ref "R137") (pin "1") (pinfunction "1_1") (pintype "passive"))
      (node (ref "SW9") (pin "1") (pinfunction "1_1") (pintype "passive"))
      (node (ref "T26") (pin "1") (pinfunction "G_1") (pintype "passive"))
    )
    (net (code "2") (name "/DIR_CTRL1") (class "Default")
      (node (ref "IC13") (pin "10") (pinfunction "P5_10") (pintype "bidirectional"))
      (node (ref "IC13") (pin "11") (pinfunction "P6_11") (pintype "bidirectional"))
      (node (ref "IC13") (pin "12") (pinfunction "P7_12") (pintype "bidirectional"))
      (node (ref "IC13") (pin "9") (pinfunction "P4_9") (pintype "bidirectional"))
      (node (ref "IC9") (pin "1") (pinfunction "1DE_1") (pintype "input"))
      (node (ref "IC9") (pin "12") (pinfunction "4DE_12") (pintype "input"))
      (node (ref "IC9") (pin "19") (pinfunction "~{3RE}_19") (pintype "input"))
      (node (ref "IC9") (pin "21") (pinfunction "~{4RE}_21") (pintype "input"))
      (node (ref "IC9") (pin "40") (pinfunction "~{1RE}_40") (pintype "input"))
      (node (ref "IC9") (pin "42") (pinfunction "~{2RE}_42") (pintype "input"))
      (node (ref "IC9") (pin "5") (pinfunction "2DE_5") (pintype "input"))
      (node (ref "IC9") (pin "8") (pinfunction "3DE_8") (pintype "input"))
      (node (ref "R153") (pin "2") (pinfunction "2_2") (pintype "passive"))
      (node (ref "R156") (pin "1") (pinfunction "1_1") (pintype "passive"))
      (node (ref "SW9") (pin "2") (pinfunction "2_2") (pintype "passive"))
      (node (ref "T28") (pin "1") (pinfunction "G_1") (pintype "passive"))
    )
    (net (code "3") (name "/I2C_SCL") (class "Default")
      (node (ref "B8") (pin "1") (pinfunction "1_1") (pintype "bidirectional"))
      (node (ref "IC13") (pin "14") (pinfunction "SCL_14") (pintype "input"))
      (node (ref "IC32") (pin "1") (pinfunction "SCL_1") (pintype "input"))
      (node (ref "J37") (pin "27") (pinfunction "27_27") (pintype "bidirectional"))
    )
    (net (code "4") (name "/I2C_SDA") (class "Default")
      (node (ref "B7") (pin "1") (pinfunction "1_1") (pintype "bidirectional"))
      (node (ref "IC13") (pin "15") (pinfunction "SDA_15") (pintype "bidirectional"))
      (node (ref "IC32") (pin "3") (pinfunction "SDA_3") (pintype "bidirectional"))
      (node (ref "J37") (pin "26") (pinfunction "26_26") (pintype "bidirectional"))
    )
    (net (code "5") (name "/IO0") (class "Default")
      (node (ref "J1") (pin "4") (pinfunction "4_4") (pintype "bidirectional"))
      (node (ref "R13") (pin "1") (pinfunction "1_1") (pintype "passive"))
      (node (ref "R139") (pin "2") (pinfunction "2_2") (pintype "passive"))
    )
    (net (code "6") (name "/IO1") (class "Default")
      (node (ref "J1") (pin "2") (pinfunction "2_2") (pintype "bidirectional"))
      (node (ref "R14") (pin "1") (pinfunction "1_1") (pintype "passive"))
      (node (ref "R142") (pin "2") (pinfunction "2_2") (pintype "passive"))
    )
    (net (code "7") (name "/IO2") (class "Default")
      (node (ref "J2") (pin "4") (pinfunction "4_4") (pintype "bidirectional"))
      (node (ref "R145") (pin "2") (pinfunction "2_2") (pintype "passive"))
      (node (ref "R15") (pin "1") (pinfunction "1_1") (pintype "passive"))
    )
    (net (code "8") (name "/IO3") (class "Default")
      (node (ref "J2") (pin "2") (pinfunction "2_2") (pintype "bidirectional"))
      (node (ref "R148") (pin "2") (pinfunction "2_2") (pintype "passive"))
      (node (ref "R16") (pin "1") (pinfunction "1_1") (pintype "passive"))
    )
    (net (code "9") (name "/IO4") (class "Default")
      (node (ref "J3") (pin "4") (pinfunction "4_4") (pintype "bidirectional"))
      (node (ref "R158") (pin "2") (pinfunction "2_2") (pintype "passive"))
      (node (ref "R20") (pin "1") (pinfunction "1_1") (pintype "passive"))
    )
    (net (code "10") (name "/IO5") (class "Default")
      (node (ref "J3") (pin "2") (pinfunction "2_2") (pintype "bidirectional"))
      (node (ref "R161") (pin "2") (pinfunction "2_2") (pintype "passive"))
      (node (ref "R21") (pin "1") (pinfunction "1_1") (pintype "passive"))
    )
    (net (code "11") (name "/IO6") (class "Default")
      (node (ref "J4") (pin "4") (pinfunction "4_4") (pintype "bidirectional"))
      (node (ref "R164") (pin "2") (pinfunction "2_2") (pintype "passive"))
      (node (ref "R22") (pin "1") (pinfunction "1_1") (pintype "passive"))
    )
    (net (code "12") (name "/IO7") (class "Default")
      (node (ref "J4") (pin "2") (pinfunction "2_2") (pintype "bidirectional"))
      (node (ref "R168") (pin "2") (pinfunction "2_2") (pintype "passive"))
      (node (ref "R23") (pin "1") (pinfunction "1_1") (pintype "passive"))
    )
    (net (code "13") (name "/LED0") (class "Default")
      (node (ref "LD2") (pin "2") (pinfunction "A_2") (pintype "passive"))
      (node (ref "R1") (pin "2") (pinfunction "2_2") (pintype "passive"))
    )
    (net (code "14") (name "/LED1") (class "Default")
      (node (ref "LD2") (pin "4") (pinfunction "A_4") (pintype "passive"))
      (node (ref "R2") (pin "2") (pinfunction "2_2") (pintype "passive"))
    )
    (net (code "15") (name "/LED2") (class "Default")
      (node (ref "LD1") (pin "4") (pinfunction "A_4") (pintype "passive"))
      (node (ref "R3") (pin "2") (pinfunction "2_2") (pintype "passive"))
    )
    (net (code "16") (name "/LED3") (class "Default")
      (node (ref "LD1") (pin "2") (pinfunction "A_2") (pintype "passive"))
      (node (ref "R4") (pin "2") (pinfunction "2_2") (pintype "passive"))
    )
    (net (code "17") (name "/LED4") (class "Default")
      (node (ref "LD8") (pin "4") (pinfunction "A_4") (pintype "passive"))
      (node (ref "R5") (pin "2") (pinfunction "2_2") (pintype "passive"))
    )
    (net (code "18") (name "/LED5") (class "Default")
      (node (ref "LD8") (pin "2") (pinfunction "A_2") (pintype "passive"))
      (node (ref "R7") (pin "2") (pinfunction "2_2") (pintype "passive"))
    )
    (net (code "19") (name "/LED6") (class "Default")
      (node (ref "LD3") (pin "4") (pinfunction "A_4") (pintype "passive"))
      (node (ref "R9") (pin "2") (pinfunction "2_2") (pintype "passive"))
    )
    (net (code "20") (name "/LED7") (class "Default")
      (node (ref "LD3") (pin "2") (pinfunction "A_2") (pintype "passive"))
      (node (ref "R11") (pin "2") (pinfunction "2_2") (pintype "passive"))
    )
    (net (code "21") (name "/LVDS0_N") (class "Default")
      (node (ref "IC21") (pin "48") (pinfunction "1B_48") (pintype "bidirectional"))
      (node (ref "J37") (pin "3") (pinfunction "3_3") (pintype "bidirectional"))
      (node (ref "R141") (pin "2") (pinfunction "2_2") (pintype "passive"))
    )
    (net (code "22") (name "/LVDS0_P") (class "Default")
      (node (ref "IC21") (pin "47") (pinfunction "1A_47") (pintype "bidirectional"))
      (node (ref "J37") (pin "2") (pinfunction "2_2") (pintype "bidirectional"))
      (node (ref "R141") (pin "1") (pinfunction "1_1") (pintype "passive"))
    )
    (net (code "23") (name "/LVDS1_N") (class "Default")
      (node (ref "IC21") (pin "4") (pinfunction "2B_4") (pintype "bidirectional"))
      (node (ref "J37") (pin "6") (pinfunction "6_6") (pintype "bidirectional"))
      (node (ref "R144") (pin "2") (pinfunction "2_2") (pintype "passive"))
    )
    (net (code "24") (name "/LVDS1_P") (class "Default")
      (node (ref "IC21") (pin "3") (pinfunction "2A_3") (pintype "bidirectional"))
      (node (ref "J37") (pin "5") (pinfunction "5_5") (pintype "bidirectional"))
      (node (ref "R144") (pin "1") (pinfunction "1_1") (pintype "passive"))
    )
    (net (code "25") (name "/LVDS2_N") (class "Default")
      (node (ref "IC21") (pin "10") (pinfunction "3B_10") (pintype "bidirectional"))
      (node (ref "J37") (pin "9") (pinfunction "9_9") (pintype "bidirectional"))
      (node (ref "R147") (pin "2") (pinfunction "2_2") (pintype "passive"))
    )
    (net (code "26") (name "/LVDS2_P") (class "Default")
      (node (ref "IC21") (pin "9") (pinfunction "3A_9") (pintype "bidirectional"))
      (node (ref "J37") (pin "8") (pinfunction "8_8") (pintype "bidirectional"))
      (node (ref "R147") (pin "1") (pinfunction "1_1") (pintype "passive"))
    )
    (net (code "27") (name "/LVDS3_N") (class "Default")
      (node (ref "IC21") (pin "14") (pinfunction "4B_14") (pintype "bidirectional"))
      (node (ref "J37") (pin "12") (pinfunction "12_12") (pintype "bidirectional"))
      (node (ref "R151") (pin "2") (pinfunction "2_2") (pintype "passive"))
    )
    (net (code "28") (name "/LVDS3_P") (class "Default")
      (node (ref "IC21") (pin "13") (pinfunction "4A_13") (pintype "bidirectional"))
      (node (ref "J37") (pin "11") (pinfunction "11_11") (pintype "bidirectional"))
      (node (ref "R151") (pin "1") (pinfunction "1_1") (pintype "passive"))
    )
    (net (code "29") (name "/LVDS4_N") (class "Default")
      (node (ref "IC9") (pin "48") (pinfunction "1B_48") (pintype "bidirectional"))
      (node (ref "J37") (pin "15") (pinfunction "15_15") (pintype "bidirectional"))
      (node (ref "R160") (pin "2") (pinfunction "2_2") (pintype "passive"))
    )
    (net (code "30") (name "/LVDS4_P") (class "Default")
      (node (ref "IC9") (pin "47") (pinfunction "1A_47") (pintype "bidirectional"))
      (node (ref "J37") (pin "14") (pinfunction "14_14") (pintype "bidirectional"))
      (node (ref "R160") (pin "1") (pinfunction "1_1") (pintype "passive"))
    )
    (net (code "31") (name "/LVDS5_N") (class "Default")
      (node (ref "IC9") (pin "4") (pinfunction "2B_4") (pintype "bidirectional"))
      (node (ref "J37") (pin "18") (pinfunction "18_18") (pintype "bidirectional"))
      (node (ref "R163") (pin "2") (pinfunction "2_2") (pintype "passive"))
    )
    (net (code "32") (name "/LVDS5_P") (class "Default")
      (node (ref "IC9") (pin "3") (pinfunction "2A_3") (pintype "bidirectional"))
      (node (ref "J37") (pin "17") (pinfunction "17_17") (pintype "bidirectional"))
      (node (ref "R163") (pin "1") (pinfunction "1_1") (pintype "passive"))
    )
    (net (code "33") (name "/LVDS6_N") (class "Default")
      (node (ref "IC9") (pin "10") (pinfunction "3B_10") (pintype "bidirectional"))
      (node (ref "J37") (pin "21") (pinfunction "21_21") (pintype "bidirectional"))
      (node (ref "R166") (pin "2") (pinfunction "2_2") (pintype "passive"))
    )
    (net (code "34") (name "/LVDS6_P") (class "Default")
      (node (ref "IC9") (pin "9") (pinfunction "3A_9") (pintype "bidirectional"))
      (node (ref "J37") (pin "20") (pinfunction "20_20") (pintype "bidirectional"))
      (node (ref "R166") (pin "1") (pinfunction "1_1") (pintype "passive"))
    )
    (net (code "35") (name "/LVDS7_N") (class "Default")
      (node (ref "IC9") (pin "14") (pinfunction "4B_14") (pintype "bidirectional"))
      (node (ref "J37") (pin "24") (pinfunction "24_24") (pintype "bidirectional"))
      (node (ref "R170") (pin "2") (pinfunction "2_2") (pintype "passive"))
    )
    (net (code "36") (name "/LVDS7_P") (class "Default")
      (node (ref "IC9") (pin "13") (pinfunction "4A_13") (pintype "bidirectional"))
      (node (ref "J37") (pin "23") (pinfunction "23_23") (pintype "bidirectional"))
      (node (ref "R170") (pin "1") (pinfunction "1_1") (pintype "passive"))
    )
    (net (code "37") (name "/TERM_IO0") (class "Default")
      (node (ref "R1") (pin "1") (pinfunction "1_1") (pintype "passive"))
      (node (ref "SW1") (pin "8") (pinfunction "8_8") (pintype "passive"))
      (node (ref "T1") (pin "1") (pinfunction "G_1") (pintype "passive"))
    )
    (net (code "38") (name "/TERM_IO1") (class "Default")
      (node (ref "R2") (pin "1") (pinfunction "1_1") (pintype "passive"))
      (node (ref "SW1") (pin "7") (pinfunction "7_7") (pintype "passive"))
      (node (ref "T2") (pin "1") (pinfunction "G_1") (pintype "passive"))
    )
    (net (code "39") (name "/TERM_IO2") (class "Default")
      (node (ref "R3") (pin "1") (pinfunction "1_1") (pintype "passive"))
      (node (ref "SW1") (pin "6") (pinfunction "6_6") (pintype "passive"))
      (node (ref "T3") (pin "1") (pinfunction "G_1") (pintype "passive"))
    )
    (net (code "40") (name "/TERM_IO3") (class "Default")
      (node (ref "R4") (pin "1") (pinfunction "1_1") (pintype "passive"))
      (node (ref "SW1") (pin "5") (pinfunction "5_5") (pintype "passive"))
      (node (ref "T4") (pin "1") (pinfunction "G_1") (pintype "passive"))
    )
    (net (code "41") (name "/TERM_IO4") (class "Default")
      (node (ref "R5") (pin "1") (pinfunction "1_1") (pintype "passive"))
      (node (ref "SW2") (pin "8") (pinfunction "8_8") (pintype "passive"))
      (node (ref "T5") (pin "1") (pinfunction "G_1") (pintype "passive"))
    )
    (net (code "42") (name "/TERM_IO5") (class "Default")
      (node (ref "R7") (pin "1") (pinfunction "1_1") (pintype "passive"))
      (node (ref "SW2") (pin "7") (pinfunction "7_7") (pintype "passive"))
      (node (ref "T6") (pin "1") (pinfunction "G_1") (pintype "passive"))
    )
    (net (code "43") (name "/TERM_IO6") (class "Default")
      (node (ref "R9") (pin "1") (pinfunction "1_1") (pintype "passive"))
      (node (ref "SW2") (pin "6") (pinfunction "6_6") (pintype "passive"))
      (node (ref "T7") (pin "1") (pinfunction "G_1") (pintype "passive"))
    )
    (net (code "44") (name "/TERM_IO7") (class "Default")
      (node (ref "R11") (pin "1") (pinfunction "1_1") (pintype "passive"))
      (node (ref "SW2") (pin "5") (pinfunction "5_5") (pintype "passive"))
      (node (ref "T8") (pin "1") (pinfunction "G_1") (pintype "passive"))
    )
    (net (code "45") (name "GND") (class "Default")
      (node (ref "B1") (pin "1") (pinfunction "1_1") (pintype "bidirectional"))
      (node (ref "B2") (pin "1") (pinfunction "1_1") (pintype "bidirectional"))
      (node (ref "B4") (pin "1") (pinfunction "1_1") (pintype "bidirectional"))
      (node (ref "C37") (pin "1") (pinfunction "1_1") (pintype "passive"))
      (node (ref "C38") (pin "1") (pinfunction "1_1") (pintype "passive"))
      (node (ref "IC10") (pin "9") (pinfunction "GND2_9") (pintype "power_in"))
      (node (ref "IC11") (pin "8") (pinfunction "GND1_8") (pintype "power_in"))
      (node (ref "IC13") (pin "1") (pinfunction "A0_1") (pintype "input"))
      (node (ref "IC13") (pin "8") (pinfunction "GND_8") (pintype "power_in"))
      (node (ref "IC21") (pin "18") (pinfunction "GND_18") (pintype "power_in"))
      (node (ref "IC21") (pin "23") (pinfunction "GND_23") (pintype "power_in"))
      (node (ref "IC21") (pin "27") (pinfunction "GND_27") (pintype "power_in"))
      (node (ref "IC21") (pin "31") (pinfunction "GND_31") (pintype "power_in"))
      (node (ref "IC21") (pin "34") (pinfunction "GND_34") (pintype "power_in"))
      (node (ref "IC21") (pin "38") (pinfunction "GND_38") (pintype "power_in"))
      (node (ref "IC21") (pin "43") (pinfunction "GND_43") (pintype "power_in"))
      (node (ref "IC21") (pin "49") (pinfunction "EP_49") (pintype "power_in"))
      (node (ref "IC21") (pin "6") (pinfunction "GND_6") (pintype "power_in"))
      (node (ref "IC21") (pin "7") (pinfunction "GND_7") (pintype "power_in"))
      (node (ref "IC22") (pin "9") (pinfunction "GND2_9") (pintype "power_in"))
      (node (ref "IC28") (pin "8") (pinfunction "GND1_8") (pintype "power_in"))
      (node (ref "IC32") (pin "2") (pinfunction "VSS_2") (pintype "power_in"))
      (node (ref "IC9") (pin "18") (pinfunction "GND_18") (pintype "power_in"))
      (node (ref "IC9") (pin "23") (pinfunction "GND_23") (pintype "power_in"))
      (node (ref "IC9") (pin "27") (pinfunction "GND_27") (pintype "power_in"))
      (node (ref "IC9") (pin "31") (pinfunction "GND_31") (pintype "power_in"))
      (node (ref "IC9") (pin "34") (pinfunction "GND_34") (pintype "power_in"))
      (node (ref "IC9") (pin "38") (pinfunction "GND_38") (pintype "power_in"))
      (node (ref "IC9") (pin "43") (pinfunction "GND_43") (pintype "power_in"))
      (node (ref "IC9") (pin "49") (pinfunction "EP_49") (pintype "power_in"))
      (node (ref "IC9") (pin "6") (pinfunction "GND_6") (pintype "power_in"))
      (node (ref "IC9") (pin "7") (pinfunction "GND_7") (pintype "power_in"))
      (node (ref "J37") (pin "1") (pinfunction "1_1") (pintype "bidirectional"))
      (node (ref "J37") (pin "10") (pinfunction "10_10") (pintype "bidirectional"))
      (node (ref "J37") (pin "13") (pinfunction "13_13") (pintype "bidirectional"))
      (node (ref "J37") (pin "16") (pinfunction "16_16") (pintype "bidirectional"))
      (node (ref "J37") (pin "19") (pinfunction "19_19") (pintype "bidirectional"))
      (node (ref "J37") (pin "22") (pinfunction "22_22") (pintype "bidirectional"))
      (node (ref "J37") (pin "25") (pinfunction "25_25") (pintype "bidirectional"))
      (node (ref "J37") (pin "4") (pinfunction "4_4") (pintype "bidirectional"))
      (node (ref "J37") (pin "7") (pinfunction "7_7") (pintype "bidirectional"))
      (node (ref "R138") (pin "2") (pinfunction "2_2") (pintype "passive"))
      (node (ref "R152") (pin "2") (pinfunction "2_2") (pintype "passive"))
      (node (ref "R157") (pin "2") (pinfunction "2_2") (pintype "passive"))
      (node (ref "R171") (pin "2") (pinfunction "2_2") (pintype "passive"))
      (node (ref "SW9") (pin "3") (pinfunction "3_3") (pintype "passive"))
      (node (ref "SW9") (pin "4") (pinfunction "4_4") (pintype "passive"))
      (node (ref "T26") (pin "2") (pinfunction "S_2") (pintype "passive"))
      (node (ref "T28") (pin "2") (pinfunction "S_2") (pintype "passive"))
    )
    (net (code "46") (name "GND_ISO1") (class "Default")
      (node (ref "IC22") (pin "8") (pinfunction "GND1_8") (pintype "power_in"))
      (node (ref "IC28") (pin "11") (pinfunction "B5_11") (pintype "input"))
      (node (ref "IC28") (pin "9") (pinfunction "GND2_9") (pintype "power_in"))
      (node (ref "IC29") (pin "11") (pinfunction "GND_11") (pintype "power_in"))
      (node (ref "IC29") (pin "2") (pinfunction "GND_2") (pintype "power_in"))
      (node (ref "IC29") (pin "5") (pinfunction "GND_5") (pintype "power_in"))
      (node (ref "IC29") (pin "8") (pinfunction "GND_8") (pintype "power_in"))
      (node (ref "IC3") (pin "1") (pinfunction "VSS_1") (pintype "power_in"))
      (node (ref "J1") (pin "1") (pinfunction "1_1") (pintype "bidirectional"))
      (node (ref "J1") (pin "3") (pinfunction "3_3") (pintype "bidirectional"))
      (node (ref "J2") (pin "1") (pinfunction "1_1") (pintype "bidirectional"))
      (node (ref "J2") (pin "3") (pinfunction "3_3") (pintype "bidirectional"))
      (node (ref "LD1") (pin "1") (pinfunction "C_1") (pintype "passive"))
      (node (ref "LD1") (pin "3") (pinfunction "C_3") (pintype "passive"))
      (node (ref "LD2") (pin "1") (pinfunction "C_1") (pintype "passive"))
      (node (ref "LD2") (pin "3") (pinfunction "C_3") (pintype "passive"))
      (node (ref "R12") (pin "1") (pinfunction "1_1") (pintype "passive"))
      (node (ref "R140") (pin "1") (pinfunction "1_1") (pintype "passive"))
      (node (ref "R143") (pin "1") (pinfunction "1_1") (pintype "passive"))
      (node (ref "R146") (pin "1") (pinfunction "1_1") (pintype "passive"))
      (node (ref "R149") (pin "1") (pinfunction "1_1") (pintype "passive"))
      (node (ref "T1") (pin "2") (pinfunction "S_2") (pintype "passive"))
      (node (ref "T2") (pin "2") (pinfunction "S_2") (pintype "passive"))
      (node (ref "T27") (pin "2") (pinfunction "S_2") (pintype "passive"))
      (node (ref "T3") (pin "2") (pinfunction "S_2") (pintype "passive"))
      (node (ref "T4") (pin "2") (pinfunction "S_2") (pintype "passive"))
    )
    (net (code "47") (name "GND_ISO2") (class "Default")
      (node (ref "IC10") (pin "8") (pinfunction "GND1_8") (pintype "power_in"))
      (node (ref "IC11") (pin "11") (pinfunction "B5_11") (pintype "input"))
      (node (ref "IC11") (pin "9") (pinfunction "GND2_9") (pintype "power_in"))
      (node (ref "IC4") (pin "1") (pinfunction "VSS_1") (pintype "power_in"))
      (node (ref "IC8") (pin "11") (pinfunction "GND_11") (pintype "power_in"))
      (node (ref "IC8") (pin "2") (pinfunction "GND_2") (pintype "power_in"))
      (node (ref "IC8") (pin "5") (pinfunction "GND_5") (pintype "power_in"))
      (node (ref "IC8") (pin "8") (pinfunction "GND_8") (pintype "power_in"))
      (node (ref "J3") (pin "1") (pinfunction "1_1") (pintype "bidirectional"))
      (node (ref "J3") (pin "3") (pinfunction "3_3") (pintype "bidirectional"))
      (node (ref "J4") (pin "1") (pinfunction "1_1") (pintype "bidirectional"))
      (node (ref "J4") (pin "3") (pinfunction "3_3") (pintype "bidirectional"))
      (node (ref "LD3") (pin "1") (pinfunction "C_1") (pintype "passive"))
      (node (ref "LD3") (pin "3") (pinfunction "C_3") (pintype "passive"))
      (node (ref "LD8") (pin "1") (pinfunction "C_1") (pintype "passive"))
      (node (ref "LD8") (pin "3") (pinfunction "C_3") (pintype "passive"))
      (node (ref "R159") (pin "1") (pinfunction "1_1") (pintype "passive"))
      (node (ref "R162") (pin "1") (pinfunction "1_1") (pintype "passive"))
      (node (ref "R165") (pin "1") (pinfunction "1_1") (pintype "passive"))
      (node (ref "R169") (pin "1") (pinfunction "1_1") (pintype "passive"))
      (node (ref "R19") (pin "1") (pinfunction "1_1") (pintype "passive"))
      (node (ref "T29") (pin "2") (pinfunction "S_2") (pintype "passive"))
      (node (ref "T5") (pin "2") (pinfunction "S_2") (pintype "passive"))
      (node (ref "T6") (pin "2") (pinfunction "S_2") (pintype "passive"))
      (node (ref "T7") (pin "2") (pinfunction "S_2") (pintype "passive"))
      (node (ref "T8") (pin "2") (pinfunction "S_2") (pintype "passive"))
    )
    (net (code "48") (name "Net-(IC4-RST)") (class "Default")
      (node (ref "IC4") (pin "2") (pinfunction "RST_2") (pintype "output"))
      (node (ref "IC8") (pin "13") (pinfunction "OE_13") (pintype "input"))
      (node (ref "R19") (pin "2") (pinfunction "2_2") (pintype "passive"))
    )
    (net (code "49") (name "Net-(IC8-A1)") (class "Default")
      (node (ref "IC8") (pin "1") (pinfunction "A1_1") (pintype "bidirectional"))
      (node (ref "IC8") (pin "3") (pinfunction "A2_3") (pintype "bidirectional"))
      (node (ref "R169") (pin "2") (pinfunction "2_2") (pintype "passive"))
      (node (ref "R23") (pin "2") (pinfunction "2_2") (pintype "passive"))
    )
    (net (code "50") (name "Net-(IC8-A3)") (class "Default")
      (node (ref "IC8") (pin "4") (pinfunction "A3_4") (pintype "bidirectional"))
      (node (ref "IC8") (pin "6") (pinfunction "A4_6") (pintype "bidirectional"))
      (node (ref "R165") (pin "2") (pinfunction "2_2") (pintype "passive"))
      (node (ref "R22") (pin "2") (pinfunction "2_2") (pintype "passive"))
    )
    (net (code "51") (name "Net-(IC8-A5)") (class "Default")
      (node (ref "IC8") (pin "7") (pinfunction "A5_7") (pintype "bidirectional"))
      (node (ref "IC8") (pin "9") (pinfunction "A6_9") (pintype "bidirectional"))
      (node (ref "R162") (pin "2") (pinfunction "2_2") (pintype "passive"))
      (node (ref "R21") (pin "2") (pinfunction "2_2") (pintype "passive"))
    )
    (net (code "52") (name "Net-(IC8-A7)") (class "Default")
      (node (ref "IC8") (pin "10") (pinfunction "A7_10") (pintype "bidirectional"))
      (node (ref "IC8") (pin "12") (pinfunction "A8_12") (pintype "bidirectional"))
      (node (ref "R159") (pin "2") (pinfunction "2_2") (pintype "passive"))
      (node (ref "R20") (pin "2") (pinfunction "2_2") (pintype "passive"))
    )
    (net (code "53") (name "Net-(IC8-B1)") (class "Default")
      (node (ref "IC8") (pin "22") (pinfunction "B2_22") (pintype "bidirectional"))
      (node (ref "IC8") (pin "23") (pinfunction "B1_23") (pintype "bidirectional"))
      (node (ref "R33") (pin "1") (pinfunction "1_1") (pintype "passive"))
    )
    (net (code "54") (name "Net-(IC8-B3)") (class "Default")
      (node (ref "IC8") (pin "19") (pinfunction "B4_19") (pintype "bidirectional"))
      (node (ref "IC8") (pin "20") (pinfunction "B3_20") (pintype "bidirectional"))
      (node (ref "R32") (pin "1") (pinfunction "1_1") (pintype "passive"))
    )
    (net (code "55") (name "Net-(IC8-B5)") (class "Default")
      (node (ref "IC8") (pin "17") (pinfunction "B6_17") (pintype "bidirectional"))
      (node (ref "IC8") (pin "18") (pinfunction "B5_18") (pintype "bidirectional"))
      (node (ref "R31") (pin "1") (pinfunction "1_1") (pintype "passive"))
    )
    (net (code "56") (name "Net-(IC8-B7)") (class "Default")
      (node (ref "IC8") (pin "14") (pinfunction "B8_14") (pintype "bidirectional"))
      (node (ref "IC8") (pin "15") (pinfunction "B7_15") (pintype "bidirectional"))
      (node (ref "R30") (pin "1") (pinfunction "1_1") (pintype "passive"))
    )
    (net (code "57") (name "Net-(IC8-DIR)") (class "Default")
      (node (ref "IC8") (pin "24") (pinfunction "DIR_24") (pintype "input"))
      (node (ref "R172") (pin "1") (pinfunction "1_1") (pintype "passive"))
      (node (ref "T29") (pin "3") (pinfunction "D_3") (pintype "passive"))
    )
    (net (code "58") (name "Net-(IC9-1FSEN)") (class "Default")
      (node (ref "IC9") (pin "20") (pinfunction "3FSEN_20") (pintype "input"))
      (node (ref "IC9") (pin "22") (pinfunction "4FSEN_22") (pintype "input"))
      (node (ref "IC9") (pin "39") (pinfunction "1FSEN_39") (pintype "input"))
      (node (ref "IC9") (pin "41") (pinfunction "2FSEN_41") (pintype "input"))
      (node (ref "R157") (pin "1") (pinfunction "1_1") (pintype "passive"))
      (node (ref "R171") (pin "1") (pinfunction "1_1") (pintype "passive"))
    )
    (net (code "59") (name "Net-(IC10-A1)") (class "Default")
      (node (ref "IC10") (pin "2") (pinfunction "A1_2") (pintype "input"))
      (node (ref "IC11") (pin "15") (pinfunction "B1_15") (pintype "output"))
      (node (ref "R30") (pin "2") (pinfunction "2_2") (pintype "passive"))
    )
    (net (code "60") (name "Net-(IC10-A2)") (class "Default")
      (node (ref "IC10") (pin "3") (pinfunction "A2_3") (pintype "input"))
      (node (ref "IC11") (pin "14") (pinfunction "B2_14") (pintype "output"))
      (node (ref "R31") (pin "2") (pinfunction "2_2") (pintype "passive"))
    )
    (net (code "61") (name "Net-(IC10-A3)") (class "Default")
      (node (ref "IC10") (pin "4") (pinfunction "A3_4") (pintype "input"))
      (node (ref "IC11") (pin "13") (pinfunction "B3_13") (pintype "output"))
      (node (ref "R32") (pin "2") (pinfunction "2_2") (pintype "passive"))
    )
    (net (code "62") (name "Net-(IC10-A4)") (class "Default")
      (node (ref "IC10") (pin "5") (pinfunction "A4_5") (pintype "input"))
      (node (ref "IC11") (pin "12") (pinfunction "B4_12") (pintype "output"))
      (node (ref "R33") (pin "2") (pinfunction "2_2") (pintype "passive"))
    )
    (net (code "63") (name "Net-(IC10-A5)") (class "Default")
      (node (ref "IC10") (pin "6") (pinfunction "A5_6") (pintype "output"))
      (node (ref "R24") (pin "1") (pinfunction "1_1") (pintype "passive"))
      (node (ref "T29") (pin "1") (pinfunction "G_1") (pintype "passive"))
    )
    (net (code "64") (name "Net-(IC10-B1)") (class "Default")
      (node (ref "IC10") (pin "15") (pinfunction "B1_15") (pintype "output"))
      (node (ref "IC9") (pin "35") (pinfunction "1D_35") (pintype "input"))
    )
    (net (code "65") (name "Net-(IC10-B2)") (class "Default")
      (node (ref "IC10") (pin "14") (pinfunction "B2_14") (pintype "output"))
      (node (ref "IC9") (pin "32") (pinfunction "2D_32") (pintype "input"))
    )
    (net (code "66") (name "Net-(IC10-B3)") (class "Default")
      (node (ref "IC10") (pin "13") (pinfunction "B3_13") (pintype "output"))
      (node (ref "IC9") (pin "28") (pinfunction "3D_28") (pintype "input"))
    )
    (net (code "67") (name "Net-(IC10-B4)") (class "Default")
      (node (ref "IC10") (pin "12") (pinfunction "B4_12") (pintype "output"))
      (node (ref "IC9") (pin "25") (pinfunction "4D_25") (pintype "input"))
    )
    (net (code "68") (name "Net-(IC10-B5)") (class "Default")
      (node (ref "IC10") (pin "11") (pinfunction "B5_11") (pintype "input"))
      (node (ref "R154") (pin "2") (pinfunction "2_2") (pintype "passive"))
      (node (ref "R155") (pin "1") (pinfunction "1_1") (pintype "passive"))
      (node (ref "T28") (pin "3") (pinfunction "D_3") (pintype "passive"))
    )
    (net (code "69") (name "Net-(IC11-A1)") (class "Default")
      (node (ref "IC11") (pin "2") (pinfunction "A1_2") (pintype "input"))
      (node (ref "IC9") (pin "36") (pinfunction "1R_36") (pintype "output"))
    )
    (net (code "70") (name "Net-(IC11-A2)") (class "Default")
      (node (ref "IC11") (pin "3") (pinfunction "A2_3") (pintype "input"))
      (node (ref "IC9") (pin "33") (pinfunction "2R_33") (pintype "output"))
    )
    (net (code "71") (name "Net-(IC11-A3)") (class "Default")
      (node (ref "IC11") (pin "4") (pinfunction "A3_4") (pintype "input"))
      (node (ref "IC9") (pin "29") (pinfunction "3R_29") (pintype "output"))
    )
    (net (code "72") (name "Net-(IC11-A4)") (class "Default")
      (node (ref "IC11") (pin "5") (pinfunction "A4_5") (pintype "input"))
      (node (ref "IC9") (pin "26") (pinfunction "4R_26") (pintype "output"))
    )
    (net (code "73") (name "Net-(IC11-EN2)") (class "Default")
      (node (ref "IC11") (pin "10") (pinfunction "EN2_10") (pintype "input"))
      (node (ref "R24") (pin "2") (pinfunction "2_2") (pintype "passive"))
    )
    (net (code "74") (name "Net-(IC21-1D)") (class "Default")
      (node (ref "IC21") (pin "35") (pinfunction "1D_35") (pintype "input"))
      (node (ref "IC22") (pin "15") (pinfunction "B1_15") (pintype "output"))
    )
    (net (code "75") (name "Net-(IC21-1FSEN)") (class "Default")
      (node (ref "IC21") (pin "20") (pinfunction "3FSEN_20") (pintype "input"))
      (node (ref "IC21") (pin "22") (pinfunction "4FSEN_22") (pintype "input"))
      (node (ref "IC21") (pin "39") (pinfunction "1FSEN_39") (pintype "input"))
      (node (ref "IC21") (pin "41") (pinfunction "2FSEN_41") (pintype "input"))
      (node (ref "R138") (pin "1") (pinfunction "1_1") (pintype "passive"))
      (node (ref "R152") (pin "1") (pinfunction "1_1") (pintype "passive"))
    )
    (net (code "76") (name "Net-(IC21-1R)") (class "Default")
      (node (ref "IC21") (pin "36") (pinfunction "1R_36") (pintype "output"))
      (node (ref "IC28") (pin "2") (pinfunction "A1_2") (pintype "input"))
    )
    (net (code "77") (name "Net-(IC21-2D)") (class "Default")
      (node (ref "IC21") (pin "32") (pinfunction "2D_32") (pintype "input"))
      (node (ref "IC22") (pin "14") (pinfunction "B2_14") (pintype "output"))
    )
    (net (code "78") (name "Net-(IC21-2R)") (class "Default")
      (node (ref "IC21") (pin "33") (pinfunction "2R_33") (pintype "output"))
      (node (ref "IC28") (pin "3") (pinfunction "A2_3") (pintype "input"))
    )
    (net (code "79") (name "Net-(IC21-3D)") (class "Default")
      (node (ref "IC21") (pin "28") (pinfunction "3D_28") (pintype "input"))
      (node (ref "IC22") (pin "13") (pinfunction "B3_13") (pintype "output"))
    )
    (net (code "80") (name "Net-(IC21-3R)") (class "Default")
      (node (ref "IC21") (pin "29") (pinfunction "3R_29") (pintype "output"))
      (node (ref "IC28") (pin "4") (pinfunction "A3_4") (pintype "input"))
    )
    (net (code "81") (name "Net-(IC21-4D)") (class "Default")
      (node (ref "IC21") (pin "25") (pinfunction "4D_25") (pintype "input"))
      (node (ref "IC22") (pin "12") (pinfunction "B4_12") (pintype "output"))
    )
    (net (code "82") (name "Net-(IC21-4R)") (class "Default")
      (node (ref "IC21") (pin "26") (pinfunction "4R_26") (pintype "output"))
      (node (ref "IC28") (pin "5") (pinfunction "A4_5") (pintype "input"))
    )
    (net (code "83") (name "Net-(IC22-A1)") (class "Default")
      (node (ref "IC22") (pin "2") (pinfunction "A1_2") (pintype "input"))
      (node (ref "IC28") (pin "15") (pinfunction "B1_15") (pintype "output"))
      (node (ref "R26") (pin "2") (pinfunction "2_2") (pintype "passive"))
    )
    (net (code "84") (name "Net-(IC22-A2)") (class "Default")
      (node (ref "IC22") (pin "3") (pinfunction "A2_3") (pintype "input"))
      (node (ref "IC28") (pin "14") (pinfunction "B2_14") (pintype "output"))
      (node (ref "R27") (pin "2") (pinfunction "2_2") (pintype "passive"))
    )
    (net (code "85") (name "Net-(IC22-A3)") (class "Default")
      (node (ref "IC22") (pin "4") (pinfunction "A3_4") (pintype "input"))
      (node (ref "IC28") (pin "13") (pinfunction "B3_13") (pintype "output"))
      (node (ref "R28") (pin "2") (pinfunction "2_2") (pintype "passive"))
    )
    (net (code "86") (name "Net-(IC22-A4)") (class "Default")
      (node (ref "IC22") (pin "5") (pinfunction "A4_5") (pintype "input"))
      (node (ref "IC28") (pin "12") (pinfunction "B4_12") (pintype "output"))
      (node (ref "R29") (pin "2") (pinfunction "2_2") (pintype "passive"))
    )
    (net (code "87") (name "Net-(IC22-A5)") (class "Default")
      (node (ref "IC22") (pin "6") (pinfunction "A5_6") (pintype "output"))
      (node (ref "R17") (pin "1") (pinfunction "1_1") (pintype "passive"))
      (node (ref "T27") (pin "1") (pinfunction "G_1") (pintype "passive"))
    )
    (net (code "88") (name "Net-(IC22-B5)") (class "Default")
      (node (ref "IC22") (pin "11") (pinfunction "B5_11") (pintype "input"))
      (node (ref "R135") (pin "2") (pinfunction "2_2") (pintype "passive"))
      (node (ref "R136") (pin "1") (pinfunction "1_1") (pintype "passive"))
      (node (ref "T26") (pin "3") (pinfunction "D_3") (pintype "passive"))
    )
    (net (code "89") (name "Net-(IC28-EN2)") (class "Default")
      (node (ref "IC28") (pin "10") (pinfunction "EN2_10") (pintype "input"))
      (node (ref "R17") (pin "2") (pinfunction "2_2") (pintype "passive"))
    )
    (net (code "90") (name "Net-(IC29-A1)") (class "Default")
      (node (ref "IC29") (pin "1") (pinfunction "A1_1") (pintype "bidirectional"))
      (node (ref "IC29") (pin "3") (pinfunction "A2_3") (pintype "bidirectional"))
      (node (ref "R149") (pin "2") (pinfunction "2_2") (pintype "passive"))
      (node (ref "R16") (pin "2") (pinfunction "2_2") (pintype "passive"))
    )
    (net (code "91") (name "Net-(IC29-A3)") (class "Default")
      (node (ref "IC29") (pin "4") (pinfunction "A3_4") (pintype "bidirectional"))
      (node (ref "IC29") (pin "6") (pinfunction "A4_6") (pintype "bidirectional"))
      (node (ref "R146") (pin "2") (pinfunction "2_2") (pintype "passive"))
      (node (ref "R15") (pin "2") (pinfunction "2_2") (pintype "passive"))
    )
    (net (code "92") (name "Net-(IC29-A5)") (class "Default")
      (node (ref "IC29") (pin "7") (pinfunction "A5_7") (pintype "bidirectional"))
      (node (ref "IC29") (pin "9") (pinfunction "A6_9") (pintype "bidirectional"))
      (node (ref "R14") (pin "2") (pinfunction "2_2") (pintype "passive"))
      (node (ref "R143") (pin "2") (pinfunction "2_2") (pintype "passive"))
    )
    (net (code "93") (name "Net-(IC29-A7)") (class "Default")
      (node (ref "IC29") (pin "10") (pinfunction "A7_10") (pintype "bidirectional"))
      (node (ref "IC29") (pin "12") (pinfunction "A8_12") (pintype "bidirectional"))
      (node (ref "R13") (pin "2") (pinfunction "2_2") (pintype "passive"))
      (node (ref "R140") (pin "2") (pinfunction "2_2") (pintype "passive"))
    )
    (net (code "94") (name "Net-(IC29-B1)") (class "Default")
      (node (ref "IC29") (pin "22") (pinfunction "B2_22") (pintype "bidirectional"))
      (node (ref "IC29") (pin "23") (pinfunction "B1_23") (pintype "bidirectional"))
      (node (ref "R29") (pin "1") (pinfunction "1_1") (pintype "passive"))
    )
    (net (code "95") (name "Net-(IC29-B3)") (class "Default")
      (node (ref "IC29") (pin "19") (pinfunction "B4_19") (pintype "bidirectional"))
      (node (ref "IC29") (pin "20") (pinfunction "B3_20") (pintype "bidirectional"))
      (node (ref "R28") (pin "1") (pinfunction "1_1") (pintype "passive"))
    )
    (net (code "96") (name "Net-(IC29-B5)") (class "Default")
      (node (ref "IC29") (pin "17") (pinfunction "B6_17") (pintype "bidirectional"))
      (node (ref "IC29") (pin "18") (pinfunction "B5_18") (pintype "bidirectional"))
      (node (ref "R27") (pin "1") (pinfunction "1_1") (pintype "passive"))
    )
    (net (code "97") (name "Net-(IC29-B7)") (class "Default")
      (node (ref "IC29") (pin "14") (pinfunction "B8_14") (pintype "bidirectional"))
      (node (ref "IC29") (pin "15") (pinfunction "B7_15") (pintype "bidirectional"))
      (node (ref "R26") (pin "1") (pinfunction "1_1") (pintype "passive"))
    )
    (net (code "98") (name "Net-(IC29-DIR)") (class "Default")
      (node (ref "IC29") (pin "24") (pinfunction "DIR_24") (pintype "input"))
      (node (ref "R150") (pin "1") (pinfunction "1_1") (pintype "passive"))
      (node (ref "T27") (pin "3") (pinfunction "D_3") (pintype "passive"))
    )
    (net (code "99") (name "Net-(IC29-OE)") (class "Default")
      (node (ref "IC29") (pin "13") (pinfunction "OE_13") (pintype "input"))
      (node (ref "IC3") (pin "2") (pinfunction "RST_2") (pintype "output"))
      (node (ref "R12") (pin "2") (pinfunction "2_2") (pintype "passive"))
    )
    (net (code "100") (name "Net-(LD5A-C)") (class "Default")
      (node (ref "LD5") (pin "1") (pinfunction "C_1") (pintype "passive"))
      (node (ref "R134") (pin "1") (pinfunction "1_1") (pintype "passive"))
    )
    (net (code "101") (name "Net-(LD5B-C)") (class "Default")
      (node (ref "LD5") (pin "3") (pinfunction "C_3") (pintype "passive"))
      (node (ref "R135") (pin "1") (pinfunction "1_1") (pintype "passive"))
    )
    (net (code "102") (name "Net-(LD6A-C)") (class "Default")
      (node (ref "LD6") (pin "1") (pinfunction "C_1") (pintype "passive"))
      (node (ref "R153") (pin "1") (pinfunction "1_1") (pintype "passive"))
    )
    (net (code "103") (name "Net-(LD6B-C)") (class "Default")
      (node (ref "LD6") (pin "3") (pinfunction "C_3") (pintype "passive"))
      (node (ref "R154") (pin "1") (pinfunction "1_1") (pintype "passive"))
    )
    (net (code "104") (name "Net-(T1-D)") (class "Default")
      (node (ref "R139") (pin "1") (pinfunction "1_1") (pintype "passive"))
      (node (ref "T1") (pin "3") (pinfunction "D_3") (pintype "passive"))
    )
    (net (code "105") (name "Net-(T2-D)") (class "Default")
      (node (ref "R142") (pin "1") (pinfunction "1_1") (pintype "passive"))
      (node (ref "T2") (pin "3") (pinfunction "D_3") (pintype "passive"))
    )
    (net (code "106") (name "Net-(T3-D)") (class "Default")
      (node (ref "R145") (pin "1") (pinfunction "1_1") (pintype "passive"))
      (node (ref "T3") (pin "3") (pinfunction "D_3") (pintype "passive"))
    )
    (net (code "107") (name "Net-(T4-D)") (class "Default")
      (node (ref "R148") (pin "1") (pinfunction "1_1") (pintype "passive"))
      (node (ref "T4") (pin "3") (pinfunction "D_3") (pintype "passive"))
    )
    (net (code "108") (name "Net-(T5-D)") (class "Default")
      (node (ref "R158") (pin "1") (pinfunction "1_1") (pintype "passive"))
      (node (ref "T5") (pin "3") (pinfunction "D_3") (pintype "passive"))
    )
    (net (code "109") (name "Net-(T6-D)") (class "Default")
      (node (ref "R161") (pin "1") (pinfunction "1_1") (pintype "passive"))
      (node (ref "T6") (pin "3") (pinfunction "D_3") (pintype "passive"))
    )
    (net (code "110") (name "Net-(T7-D)") (class "Default")
      (node (ref "R164") (pin "1") (pinfunction "1_1") (pintype "passive"))
      (node (ref "T7") (pin "3") (pinfunction "D_3") (pintype "passive"))
    )
    (net (code "111") (name "Net-(T8-D)") (class "Default")
      (node (ref "R168") (pin "1") (pinfunction "1_1") (pintype "passive"))
      (node (ref "T8") (pin "3") (pinfunction "D_3") (pintype "passive"))
    )
    (net (code "112") (name "P3V3") (class "Default")
      (node (ref "B5") (pin "1") (pinfunction "1_1") (pintype "bidirectional"))
      (node (ref "IC10") (pin "10") (pinfunction "EN2_10") (pintype "input"))
      (node (ref "IC10") (pin "16") (pinfunction "VDD2_16") (pintype "power_in"))
      (node (ref "IC11") (pin "1") (pinfunction "VDD1_1") (pintype "power_in"))
      (node (ref "IC11") (pin "7") (pinfunction "EN1_7") (pintype "input"))
      (node (ref "IC21") (pin "11") (pinfunction "VCC_11") (pintype "power_in"))
      (node (ref "IC21") (pin "15") (pinfunction "VCC_15") (pintype "power_in"))
      (node (ref "IC21") (pin "16") (pinfunction "VCC_16") (pintype "power_in"))
      (node (ref "IC21") (pin "2") (pinfunction "VCC_2") (pintype "power_in"))
      (node (ref "IC21") (pin "24") (pinfunction "VCC_24") (pintype "power_in"))
      (node (ref "IC21") (pin "30") (pinfunction "PDN_30") (pintype "input"))
      (node (ref "IC21") (pin "37") (pinfunction "VCC_37") (pintype "power_in"))
      (node (ref "IC21") (pin "45") (pinfunction "VCC_45") (pintype "power_in"))
      (node (ref "IC21") (pin "46") (pinfunction "VCC_46") (pintype "power_in"))
      (node (ref "IC22") (pin "10") (pinfunction "EN2_10") (pintype "input"))
      (node (ref "IC22") (pin "16") (pinfunction "VDD2_16") (pintype "power_in"))
      (node (ref "IC28") (pin "1") (pinfunction "VDD1_1") (pintype "power_in"))
      (node (ref "IC28") (pin "7") (pinfunction "EN1_7") (pintype "input"))
      (node (ref "IC9") (pin "11") (pinfunction "VCC_11") (pintype "power_in"))
      (node (ref "IC9") (pin "15") (pinfunction "VCC_15") (pintype "power_in"))
      (node (ref "IC9") (pin "16") (pinfunction "VCC_16") (pintype "power_in"))
      (node (ref "IC9") (pin "2") (pinfunction "VCC_2") (pintype "power_in"))
      (node (ref "IC9") (pin "24") (pinfunction "VCC_24") (pintype "power_in"))
      (node (ref "IC9") (pin "30") (pinfunction "PDN_30") (pintype "input"))
      (node (ref "IC9") (pin "37") (pinfunction "VCC_37") (pintype "power_in"))
      (node (ref "IC9") (pin "45") (pinfunction "VCC_45") (pintype "power_in"))
      (node (ref "IC9") (pin "46") (pinfunction "VCC_46") (pintype "power_in"))
      (node (ref "LD5") (pin "2") (pinfunction "A_2") (pintype "passive"))
      (node (ref "LD5") (pin "4") (pinfunction "A_4") (pintype "passive"))
      (node (ref "LD6") (pin "2") (pinfunction "A_2") (pintype "passive"))
      (node (ref "LD6") (pin "4") (pinfunction "A_4") (pintype "passive"))
      (node (ref "R136") (pin "2") (pinfunction "2_2") (pintype "passive"))
      (node (ref "R137") (pin "2") (pinfunction "2_2") (pintype "passive"))
      (node (ref "R155") (pin "2") (pinfunction "2_2") (pintype "passive"))
      (node (ref "R156") (pin "2") (pinfunction "2_2") (pintype "passive"))
    )
    (net (code "113") (name "P3V3_MP") (class "Default")
      (node (ref "B3") (pin "1") (pinfunction "1_1") (pintype "bidirectional"))
      (node (ref "C37") (pin "2") (pinfunction "2_2") (pintype "passive"))
      (node (ref "C38") (pin "2") (pinfunction "2_2") (pintype "passive"))
      (node (ref "IC13") (pin "16") (pinfunction "VCC_16") (pintype "bidirectional"))
      (node (ref "IC13") (pin "2") (pinfunction "A1_2") (pintype "input"))
      (node (ref "IC13") (pin "3") (pinfunction "A2_3") (pintype "input"))
      (node (ref "IC32") (pin "4") (pinfunction "VCC_4") (pintype "power_in"))
      (node (ref "J37") (pin "30") (pinfunction "30_30") (pintype "bidirectional"))
    )
    (net (code "114") (name "P5V0_ISO1") (class "Default")
      (node (ref "IC22") (pin "1") (pinfunction "VDD1_1") (pintype "power_in"))
      (node (ref "IC22") (pin "7") (pinfunction "EN1_7") (pintype "input"))
      (node (ref "IC28") (pin "16") (pinfunction "VDD2_16") (pintype "power_in"))
      (node (ref "IC29") (pin "16") (pinfunction "VCC_16") (pintype "power_in"))
      (node (ref "IC29") (pin "21") (pinfunction "VCC_21") (pintype "power_in"))
      (node (ref "IC3") (pin "3") (pinfunction "VDD_3") (pintype "power_in"))
      (node (ref "R150") (pin "2") (pinfunction "2_2") (pintype "passive"))
      (node (ref "SW1") (pin "1") (pinfunction "1_1") (pintype "passive"))
      (node (ref "SW1") (pin "2") (pinfunction "2_2") (pintype "passive"))
      (node (ref "SW1") (pin "3") (pinfunction "3_3") (pintype "passive"))
      (node (ref "SW1") (pin "4") (pinfunction "4_4") (pintype "passive"))
    )
    (net (code "115") (name "P5V0_ISO2") (class "Default")
      (node (ref "IC10") (pin "1") (pinfunction "VDD1_1") (pintype "power_in"))
      (node (ref "IC10") (pin "7") (pinfunction "EN1_7") (pintype "input"))
      (node (ref "IC11") (pin "16") (pinfunction "VDD2_16") (pintype "power_in"))
      (node (ref "IC4") (pin "3") (pinfunction "VDD_3") (pintype "power_in"))
      (node (ref "IC8") (pin "16") (pinfunction "VCC_16") (pintype "power_in"))
      (node (ref "IC8") (pin "21") (pinfunction "VCC_21") (pintype "power_in"))
      (node (ref "R172") (pin "2") (pinfunction "2_2") (pintype "passive"))
      (node (ref "SW2") (pin "1") (pinfunction "1_1") (pintype "passive"))
      (node (ref "SW2") (pin "2") (pinfunction "2_2") (pintype "passive"))
      (node (ref "SW2") (pin "3") (pinfunction "3_3") (pintype "passive"))
      (node (ref "SW2") (pin "4") (pinfunction "4_4") (pintype "passive"))
    )
    (net (code "116") (name "P12V0") (class "Default")
      (node (ref "B6") (pin "1") (pinfunction "1_1") (pintype "bidirectional"))
      (node (ref "J37") (pin "28") (pinfunction "28_28") (pintype "bidirectional"))
      (node (ref "J37") (pin "29") (pinfunction "29_29") (pintype "bidirectional"))
    )
    (net (code "117") (name "unconnected-(IC9-NC-Pad17)") (class "Default")
      (node (ref "IC9") (pin "17") (pinfunction "NC_17") (pintype "passive"))
    )
    (net (code "118") (name "unconnected-(IC9-NC-Pad44)") (class "Default")
      (node (ref "IC9") (pin "44") (pinfunction "NC_44") (pintype "passive"))
    )
    (net (code "119") (name "unconnected-(IC11-A5-Pad6)") (class "Default")
      (node (ref "IC11") (pin "6") (pinfunction "A5_6") (pintype "output"))
    )
    (net (code "120") (name "unconnected-(IC13-~{INT}-Pad13)") (class "Default")
      (node (ref "IC13") (pin "13") (pinfunction "~{INT}_13") (pintype "output"))
    )
    (net (code "121") (name "unconnected-(IC21-NC-Pad17)") (class "Default")
      (node (ref "IC21") (pin "17") (pinfunction "NC_17") (pintype "passive"))
    )
    (net (code "122") (name "unconnected-(IC21-NC-Pad44)") (class "Default")
      (node (ref "IC21") (pin "44") (pinfunction "NC_44") (pintype "passive"))
    )
    (net (code "123") (name "unconnected-(IC28-A5-Pad6)") (class "Default")
      (node (ref "IC28") (pin "6") (pinfunction "A5_6") (pintype "output"))
    )
    (net (code "124") (name "unconnected-(IC32-NC-Pad5)") (class "Default")
      (node (ref "IC32") (pin "5") (pinfunction "NC_5") (pintype "passive"))
    )
  )
)
